# 11_MCU.net
KiCad netlist of a schematic drawn in Altium Designer
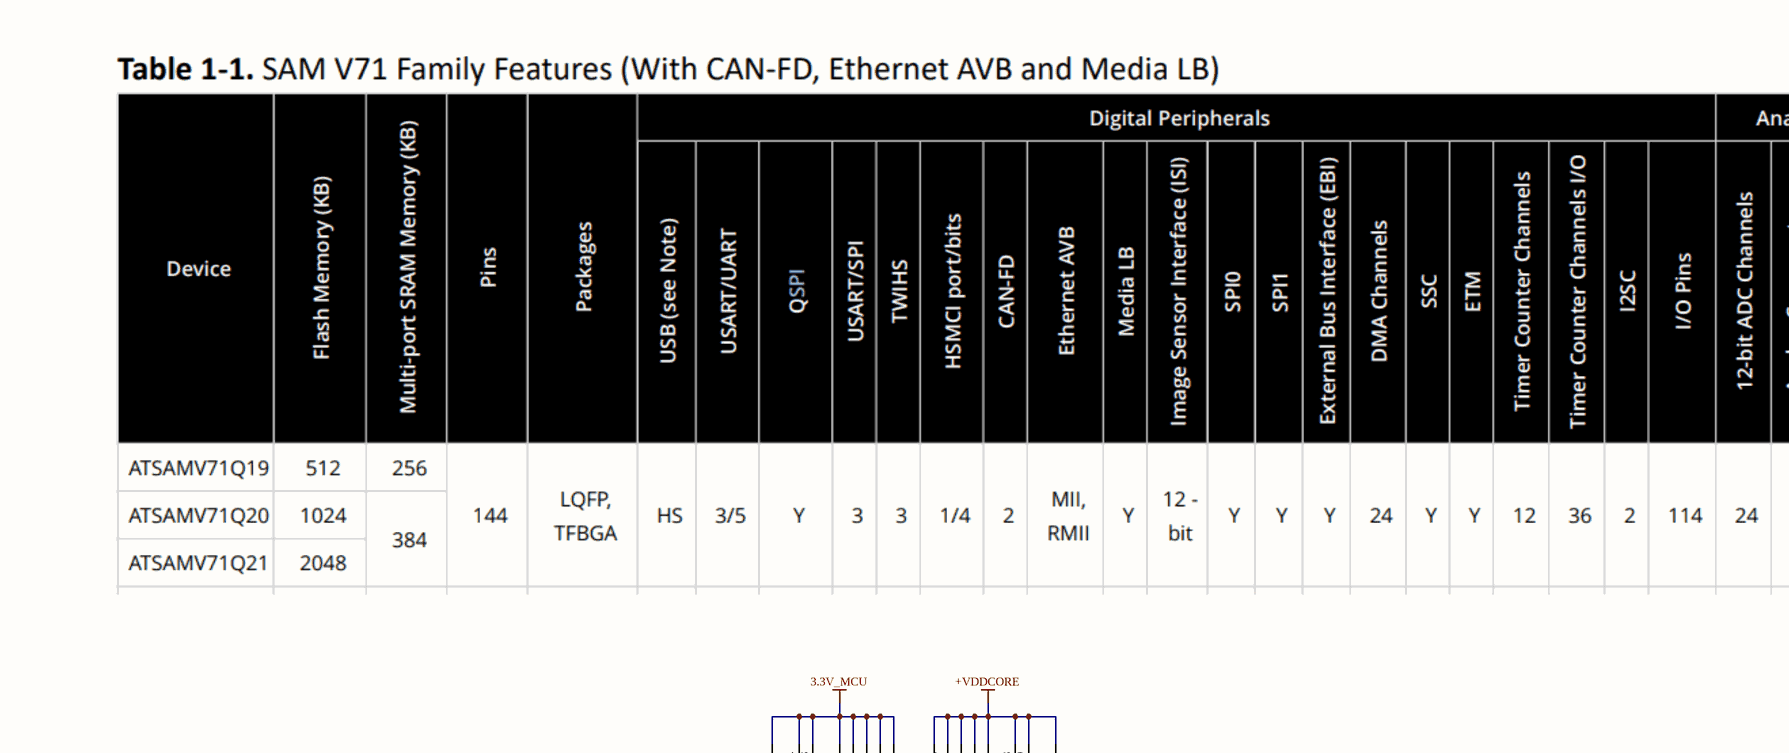
[diagram p0: 11_MCU.SchDoc, top left]
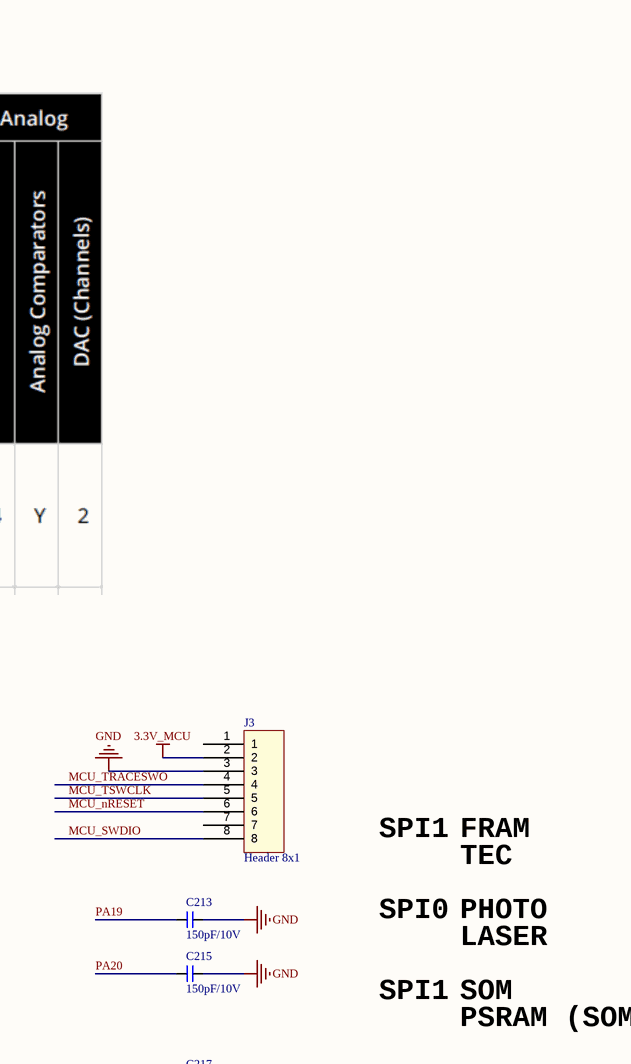
[diagram p1: 11_MCU.SchDoc, top right]
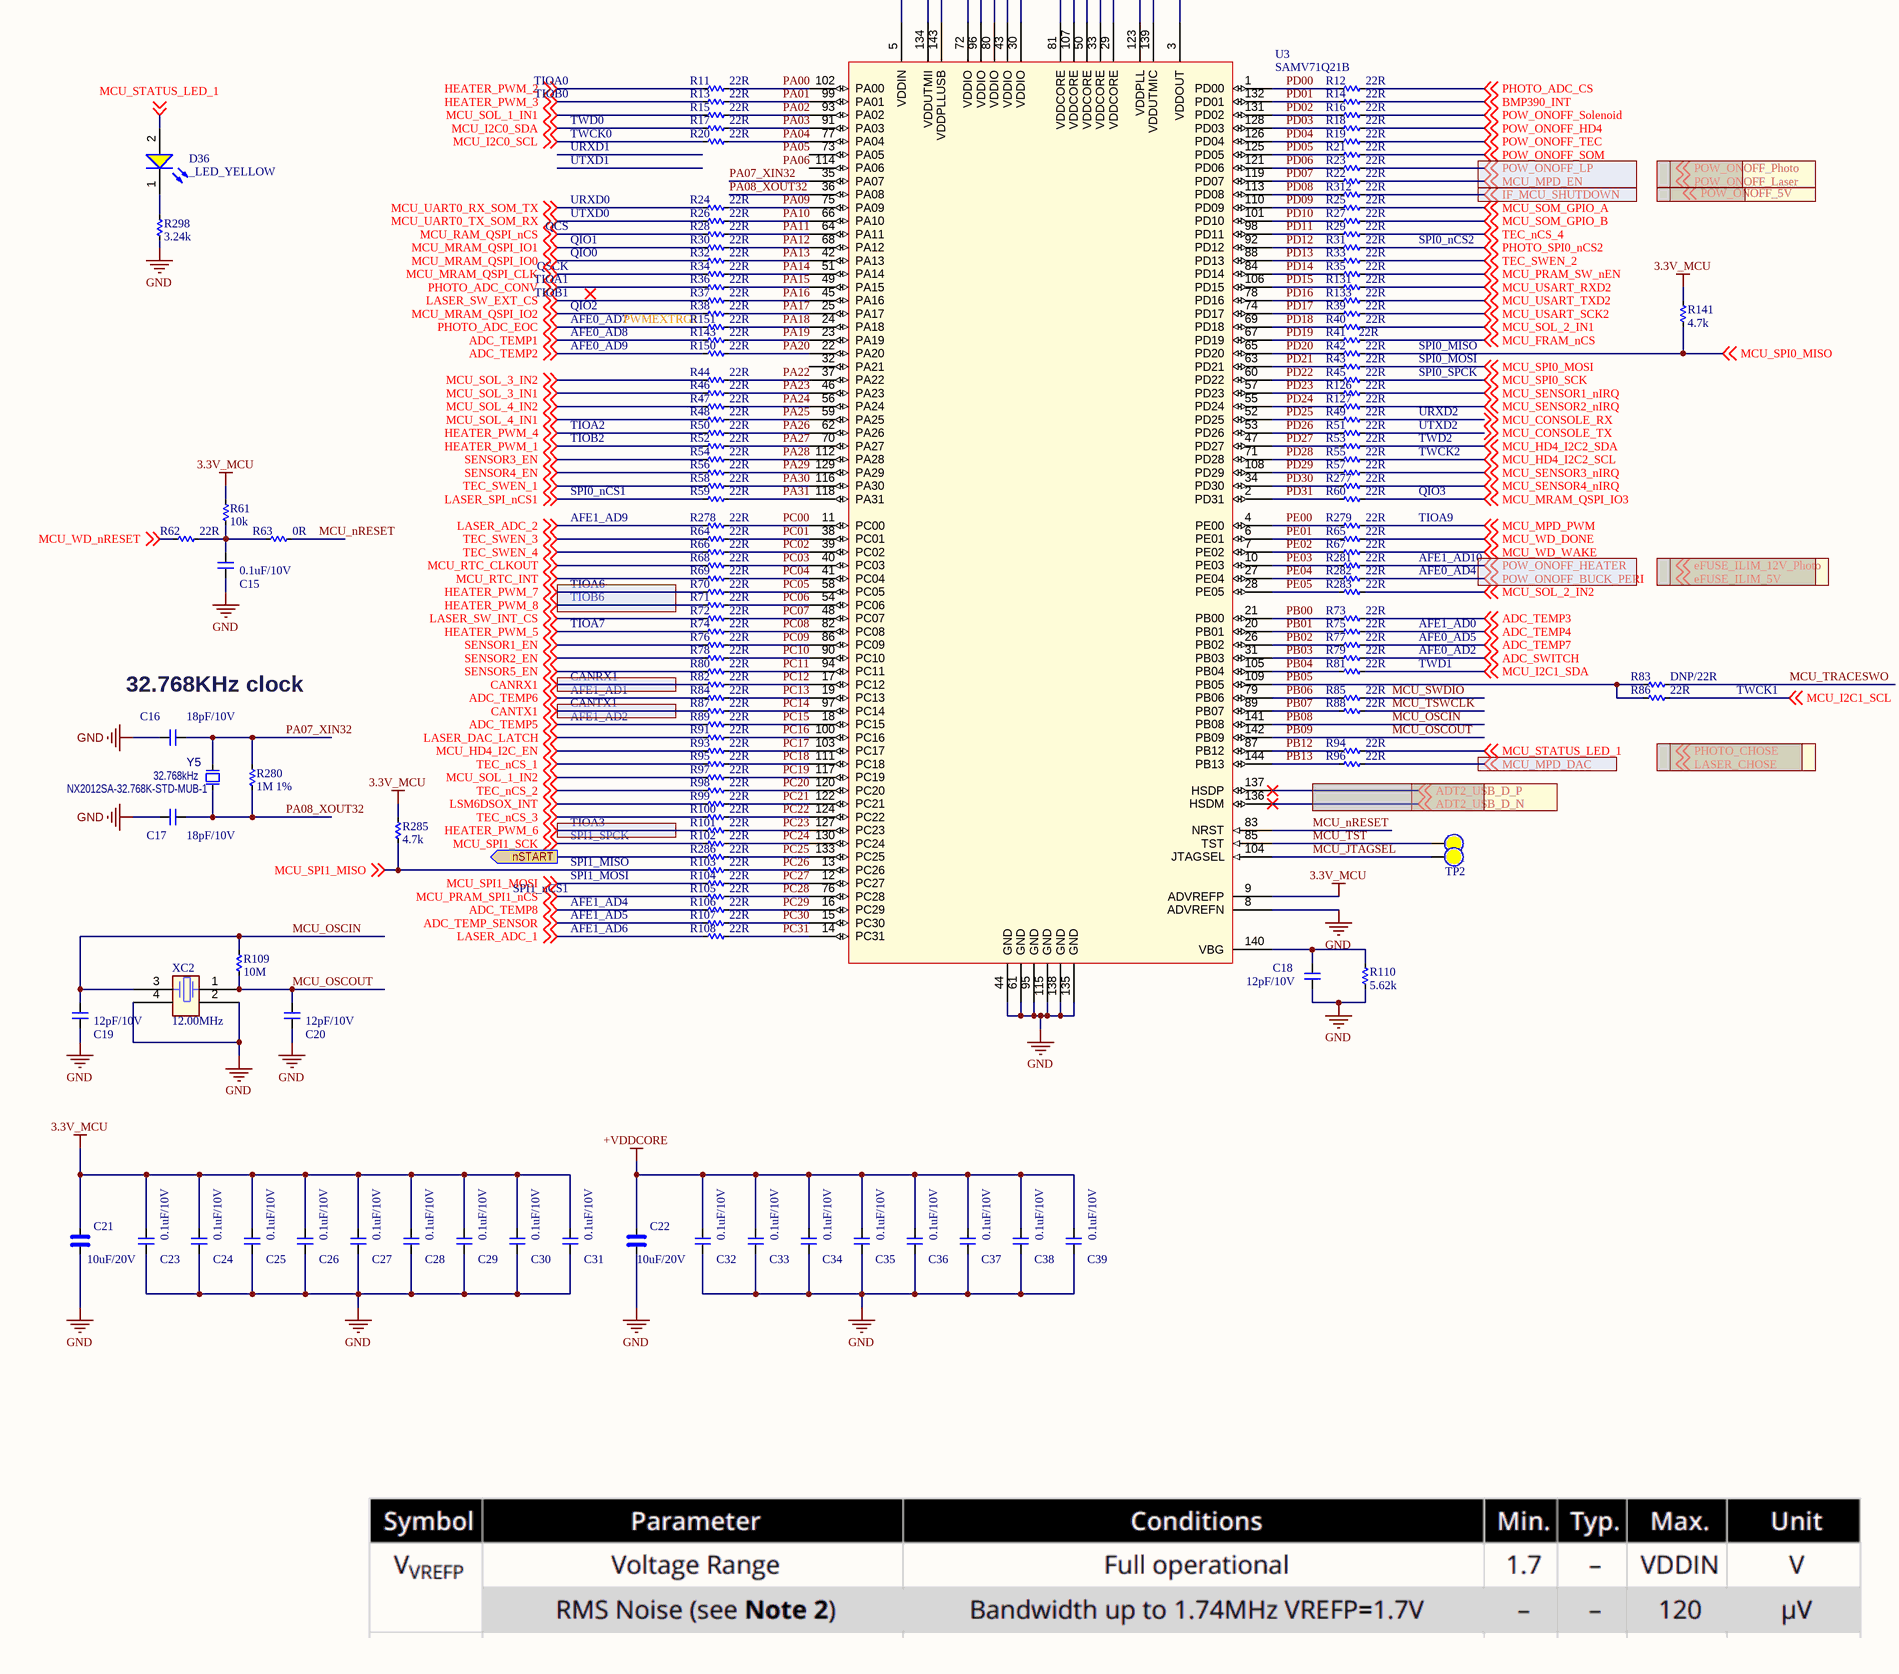
[diagram p2: 11_MCU.SchDoc, bottom left]
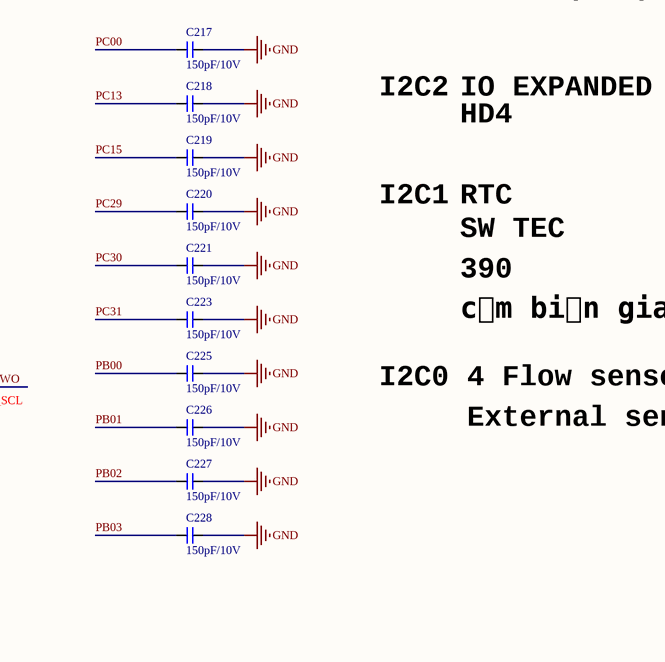
[diagram p3: 11_MCU.SchDoc, bottom right]

(export (version "E")
  (design (tool "Eeschema 10.0.6"))
  (components
    (comp (ref "C15")
      (value "0.1uF/10V")
      (footprint "CAP_C_1005X50_L")
      (description "CAP")
      (libsource (lib "LABLIB") (part "_CAP_C_2"))
    )
    (comp (ref "C16")
      (value "18pF/10V")
      (footprint "CAP_C_0603x30")
      (description "CAP")
      (libsource (lib "LABLIB") (part "_CAP_C_2"))
    )
    (comp (ref "C17")
      (value "18pF/10V")
      (footprint "CAP_C_0603x30")
      (description "CAP")
      (libsource (lib "LABLIB") (part "_CAP_C_2"))
    )
    (comp (ref "C18")
      (value "12pF/10V")
      (footprint "CAP_C_1005X50_L")
      (description "CAP")
      (libsource (lib "LABLIB") (part "_CAP_C_2"))
    )
    (comp (ref "C19")
      (value "12pF/10V")
      (footprint "CAP_C_1005X50_L")
      (description "CAP")
      (libsource (lib "LABLIB") (part "_CAP_C_2"))
    )
    (comp (ref "C20")
      (value "12pF/10V")
      (footprint "CAP_C_1005X50_L")
      (description "CAP")
      (libsource (lib "LABLIB") (part "_CAP_C_2"))
    )
    (comp (ref "C21")
      (value "10uF/20V")
      (footprint "CAP_C_2012X110")
      (description "CAP High Value")
      (libsource (lib "LABLIB") (part "_CAP_C_High_2"))
    )
    (comp (ref "C22")
      (value "10uF/20V")
      (footprint "CAP_C_2012X110")
      (description "CAP High Value")
      (libsource (lib "LABLIB") (part "_CAP_C_High_2"))
    )
    (comp (ref "C23")
      (value "0.1uF/10V")
      (footprint "CAP_C_1005X50_L")
      (description "CAP")
      (libsource (lib "LABLIB") (part "_CAP_C_2"))
    )
    (comp (ref "C24")
      (value "0.1uF/10V")
      (footprint "CAP_C_1005X50_L")
      (description "CAP")
      (libsource (lib "LABLIB") (part "_CAP_C_2"))
    )
    (comp (ref "C25")
      (value "0.1uF/10V")
      (footprint "CAP_C_1005X50_L")
      (description "CAP")
      (libsource (lib "LABLIB") (part "_CAP_C_2"))
    )
    (comp (ref "C26")
      (value "0.1uF/10V")
      (footprint "CAP_C_1005X50_L")
      (description "CAP")
      (libsource (lib "LABLIB") (part "_CAP_C_2"))
    )
    (comp (ref "C27")
      (value "0.1uF/10V")
      (footprint "CAP_C_1005X50_L")
      (description "CAP")
      (libsource (lib "LABLIB") (part "_CAP_C_2"))
    )
    (comp (ref "C28")
      (value "0.1uF/10V")
      (footprint "CAP_C_1005X50_L")
      (description "CAP")
      (libsource (lib "LABLIB") (part "_CAP_C_2"))
    )
    (comp (ref "C29")
      (value "0.1uF/10V")
      (footprint "CAP_C_1005X50_L")
      (description "CAP")
      (libsource (lib "LABLIB") (part "_CAP_C_2"))
    )
    (comp (ref "C30")
      (value "0.1uF/10V")
      (footprint "CAP_C_1005X50_L")
      (description "CAP")
      (libsource (lib "LABLIB") (part "_CAP_C_2"))
    )
    (comp (ref "C31")
      (value "0.1uF/10V")
      (footprint "CAP_C_1005X50_L")
      (description "CAP")
      (libsource (lib "LABLIB") (part "_CAP_C_2"))
    )
    (comp (ref "C32")
      (value "0.1uF/10V")
      (footprint "CAP_C_1005X50_L")
      (description "CAP")
      (libsource (lib "LABLIB") (part "_CAP_C_2"))
    )
    (comp (ref "C33")
      (value "0.1uF/10V")
      (footprint "CAP_C_1005X50_L")
      (description "CAP")
      (libsource (lib "LABLIB") (part "_CAP_C_2"))
    )
    (comp (ref "C34")
      (value "0.1uF/10V")
      (footprint "CAP_C_1005X50_L")
      (description "CAP")
      (libsource (lib "LABLIB") (part "_CAP_C_2"))
    )
    (comp (ref "C35")
      (value "0.1uF/10V")
      (footprint "CAP_C_1005X50_L")
      (description "CAP")
      (libsource (lib "LABLIB") (part "_CAP_C_2"))
    )
    (comp (ref "C36")
      (value "0.1uF/10V")
      (footprint "CAP_C_1005X50_L")
      (description "CAP")
      (libsource (lib "LABLIB") (part "_CAP_C_2"))
    )
    (comp (ref "C37")
      (value "0.1uF/10V")
      (footprint "CAP_C_1005X50_L")
      (description "CAP")
      (libsource (lib "LABLIB") (part "_CAP_C_2"))
    )
    (comp (ref "C38")
      (value "0.1uF/10V")
      (footprint "CAP_C_1005X50_L")
      (description "CAP")
      (libsource (lib "LABLIB") (part "_CAP_C_2"))
    )
    (comp (ref "C39")
      (value "0.1uF/10V")
      (footprint "CAP_C_1005X50_L")
      (description "CAP")
      (libsource (lib "LABLIB") (part "_CAP_C_2"))
    )
    (comp (ref "C213")
      (value "150pF/10V")
      (footprint "CAP_C_0603x30")
      (description "CAP")
      (libsource (lib "LABLIB") (part "_CAP_C_2"))
    )
    (comp (ref "C215")
      (value "150pF/10V")
      (footprint "CAP_C_0603x30")
      (description "CAP")
      (libsource (lib "LABLIB") (part "_CAP_C_2"))
    )
    (comp (ref "C217")
      (value "150pF/10V")
      (footprint "CAP_C_0603x30")
      (description "CAP")
      (libsource (lib "LABLIB") (part "_CAP_C_2"))
    )
    (comp (ref "C218")
      (value "150pF/10V")
      (footprint "CAP_C_0603x30")
      (description "CAP")
      (libsource (lib "LABLIB") (part "_CAP_C_2"))
    )
    (comp (ref "C219")
      (value "150pF/10V")
      (footprint "CAP_C_0603x30")
      (description "CAP")
      (libsource (lib "LABLIB") (part "_CAP_C_2"))
    )
    (comp (ref "C220")
      (value "150pF/10V")
      (footprint "CAP_C_0603x30")
      (description "CAP")
      (libsource (lib "LABLIB") (part "_CAP_C_2"))
    )
    (comp (ref "C221")
      (value "150pF/10V")
      (footprint "CAP_C_0603x30")
      (description "CAP")
      (libsource (lib "LABLIB") (part "_CAP_C_2"))
    )
    (comp (ref "C223")
      (value "150pF/10V")
      (footprint "CAP_C_0603x30")
      (description "CAP")
      (libsource (lib "LABLIB") (part "_CAP_C_2"))
    )
    (comp (ref "C225")
      (value "150pF/10V")
      (footprint "CAP_C_0603x30")
      (description "CAP")
      (libsource (lib "LABLIB") (part "_CAP_C_2"))
    )
    (comp (ref "C226")
      (value "150pF/10V")
      (footprint "CAP_C_0603x30")
      (description "CAP")
      (libsource (lib "LABLIB") (part "_CAP_C_2"))
    )
    (comp (ref "C227")
      (value "150pF/10V")
      (footprint "CAP_C_0603x30")
      (description "CAP")
      (libsource (lib "LABLIB") (part "_CAP_C_2"))
    )
    (comp (ref "C228")
      (value "150pF/10V")
      (footprint "CAP_C_0603x30")
      (description "CAP")
      (libsource (lib "LABLIB") (part "_CAP_C_2"))
    )
    (comp (ref "D36")
      (value "_LED_YELLOW")
      (footprint "LED_0402")
      (libsource (lib "LABLIB") (part "_LED_YELLOW"))
    )
    (comp (ref "J3")
      (value "Header 8x1")
      (footprint "SAMTEC_TSM-108-01-L-SV-P-TR")
      (libsource (lib "LABLIB") (part "Header 8x1"))
    )
    (comp (ref "R11")
      (value "22R")
      (footprint "RES_C_0603X30")
      (description "RES")
      (libsource (lib "LABLIB") (part "_RES_B_2"))
    )
    (comp (ref "R12")
      (value "22R")
      (footprint "RES_C_0603X30")
      (description "RES")
      (libsource (lib "LABLIB") (part "_RES_B_2"))
    )
    (comp (ref "R13")
      (value "22R")
      (footprint "RES_C_0603X30")
      (description "RES")
      (libsource (lib "LABLIB") (part "_RES_B_2"))
    )
    (comp (ref "R14")
      (value "22R")
      (footprint "RES_C_0603X30")
      (description "RES")
      (libsource (lib "LABLIB") (part "_RES_B_2"))
    )
    (comp (ref "R15")
      (value "22R")
      (footprint "RES_C_0603X30")
      (description "RES")
      (libsource (lib "LABLIB") (part "_RES_B_2"))
    )
    (comp (ref "R16")
      (value "22R")
      (footprint "RES_C_0603X30")
      (description "RES")
      (libsource (lib "LABLIB") (part "_RES_B_2"))
    )
    (comp (ref "R17")
      (value "22R")
      (footprint "RES_C_0603X30")
      (description "RES")
      (libsource (lib "LABLIB") (part "_RES_B_2"))
    )
    (comp (ref "R18")
      (value "22R")
      (footprint "RES_C_0603X30")
      (description "RES")
      (libsource (lib "LABLIB") (part "_RES_B_2"))
    )
    (comp (ref "R19")
      (value "22R")
      (footprint "RES_C_0603X30")
      (description "RES")
      (libsource (lib "LABLIB") (part "_RES_B_2"))
    )
    (comp (ref "R20")
      (value "22R")
      (footprint "RES_C_0603X30")
      (description "RES")
      (libsource (lib "LABLIB") (part "_RES_B_2"))
    )
    (comp (ref "R21")
      (value "22R")
      (footprint "RES_C_0603X30")
      (description "RES")
      (libsource (lib "LABLIB") (part "_RES_B_2"))
    )
    (comp (ref "R22")
      (value "22R")
      (footprint "RES_C_0603X30")
      (description "RES")
      (libsource (lib "LABLIB") (part "_RES_B_2"))
    )
    (comp (ref "R23")
      (value "22R")
      (footprint "RES_C_0603X30")
      (description "RES")
      (libsource (lib "LABLIB") (part "_RES_B_2"))
    )
    (comp (ref "R24")
      (value "22R")
      (footprint "RES_C_0603X30")
      (description "RES")
      (libsource (lib "LABLIB") (part "_RES_B_2"))
    )
    (comp (ref "R25")
      (value "22R")
      (footprint "RES_C_0603X30")
      (description "RES")
      (libsource (lib "LABLIB") (part "_RES_B_2"))
    )
    (comp (ref "R26")
      (value "22R")
      (footprint "RES_C_0603X30")
      (description "RES")
      (libsource (lib "LABLIB") (part "_RES_B_2"))
    )
    (comp (ref "R27")
      (value "22R")
      (footprint "RES_C_0603X30")
      (description "RES")
      (libsource (lib "LABLIB") (part "_RES_B_2"))
    )
    (comp (ref "R28")
      (value "22R")
      (footprint "RES_C_0603X30")
      (description "RES")
      (libsource (lib "LABLIB") (part "_RES_B_2"))
    )
    (comp (ref "R29")
      (value "22R")
      (footprint "RES_C_0603X30")
      (description "RES")
      (libsource (lib "LABLIB") (part "_RES_B_2"))
    )
    (comp (ref "R30")
      (value "22R")
      (footprint "RES_C_0603X30")
      (description "RES")
      (libsource (lib "LABLIB") (part "_RES_B_2"))
    )
    (comp (ref "R31")
      (value "22R")
      (footprint "RES_C_0603X30")
      (description "RES")
      (libsource (lib "LABLIB") (part "_RES_B_2"))
    )
    (comp (ref "R32")
      (value "22R")
      (footprint "RES_C_0603X30")
      (description "RES")
      (libsource (lib "LABLIB") (part "_RES_B_2"))
    )
    (comp (ref "R33")
      (value "22R")
      (footprint "RES_C_0603X30")
      (description "RES")
      (libsource (lib "LABLIB") (part "_RES_B_2"))
    )
    (comp (ref "R34")
      (value "22R")
      (footprint "RES_C_0603X30")
      (description "RES")
      (libsource (lib "LABLIB") (part "_RES_B_2"))
    )
    (comp (ref "R35")
      (value "22R")
      (footprint "RES_C_0603X30")
      (description "RES")
      (libsource (lib "LABLIB") (part "_RES_B_2"))
    )
    (comp (ref "R36")
      (value "22R")
      (footprint "RES_C_0603X30")
      (description "RES")
      (libsource (lib "LABLIB") (part "_RES_B_2"))
    )
    (comp (ref "R37")
      (value "22R")
      (footprint "RES_C_0603X30")
      (description "RES")
      (libsource (lib "LABLIB") (part "_RES_B_2"))
    )
    (comp (ref "R38")
      (value "22R")
      (footprint "RES_C_0603X30")
      (description "RES")
      (libsource (lib "LABLIB") (part "_RES_B_2"))
    )
    (comp (ref "R39")
      (value "22R")
      (footprint "RES_C_0603X30")
      (description "RES")
      (libsource (lib "LABLIB") (part "_RES_B_2"))
    )
    (comp (ref "R40")
      (value "22R")
      (footprint "RES_C_0603X30")
      (description "RES")
      (libsource (lib "LABLIB") (part "_RES_B_2"))
    )
    (comp (ref "R41")
      (value "22R")
      (footprint "RES_C_0603X30")
      (description "RES")
      (libsource (lib "LABLIB") (part "_RES_B_2"))
    )
    (comp (ref "R42")
      (value "22R")
      (footprint "RES_C_0603X30")
      (description "RES")
      (libsource (lib "LABLIB") (part "_RES_B_2"))
    )
    (comp (ref "R43")
      (value "22R")
      (footprint "RES_C_0603X30")
      (description "RES")
      (libsource (lib "LABLIB") (part "_RES_B_2"))
    )
    (comp (ref "R44")
      (value "22R")
      (footprint "RES_C_0603X30")
      (description "RES")
      (libsource (lib "LABLIB") (part "_RES_B_2"))
    )
    (comp (ref "R45")
      (value "22R")
      (footprint "RES_C_0603X30")
      (description "RES")
      (libsource (lib "LABLIB") (part "_RES_B_2"))
    )
    (comp (ref "R46")
      (value "22R")
      (footprint "RES_C_0603X30")
      (description "RES")
      (libsource (lib "LABLIB") (part "_RES_B_2"))
    )
    (comp (ref "R47")
      (value "22R")
      (footprint "RES_C_0603X30")
      (description "RES")
      (libsource (lib "LABLIB") (part "_RES_B_2"))
    )
    (comp (ref "R48")
      (value "22R")
      (footprint "RES_C_0603X30")
      (description "RES")
      (libsource (lib "LABLIB") (part "_RES_B_2"))
    )
    (comp (ref "R49")
      (value "22R")
      (footprint "RES_C_0603X30")
      (description "RES")
      (libsource (lib "LABLIB") (part "_RES_B_2"))
    )
    (comp (ref "R50")
      (value "22R")
      (footprint "RES_C_0603X30")
      (description "RES")
      (libsource (lib "LABLIB") (part "_RES_B_2"))
    )
    (comp (ref "R51")
      (value "22R")
      (footprint "RES_C_0603X30")
      (description "RES")
      (libsource (lib "LABLIB") (part "_RES_B_2"))
    )
    (comp (ref "R52")
      (value "22R")
      (footprint "RES_C_0603X30")
      (description "RES")
      (libsource (lib "LABLIB") (part "_RES_B_2"))
    )
    (comp (ref "R53")
      (value "22R")
      (footprint "RES_C_0603X30")
      (description "RES")
      (libsource (lib "LABLIB") (part "_RES_B_2"))
    )
    (comp (ref "R54")
      (value "22R")
      (footprint "RES_C_0603X30")
      (description "RES")
      (libsource (lib "LABLIB") (part "_RES_B_2"))
    )
    (comp (ref "R55")
      (value "22R")
      (footprint "RES_C_0603X30")
      (description "RES")
      (libsource (lib "LABLIB") (part "_RES_B_2"))
    )
    (comp (ref "R56")
      (value "22R")
      (footprint "RES_C_0603X30")
      (description "RES")
      (libsource (lib "LABLIB") (part "_RES_B_2"))
    )
    (comp (ref "R57")
      (value "22R")
      (footprint "RES_C_0603X30")
      (description "RES")
      (libsource (lib "LABLIB") (part "_RES_B_2"))
    )
    (comp (ref "R58")
      (value "22R")
      (footprint "RES_C_0603X30")
      (description "RES")
      (libsource (lib "LABLIB") (part "_RES_B_2"))
    )
    (comp (ref "R59")
      (value "22R")
      (footprint "RES_C_0603X30")
      (description "RES")
      (libsource (lib "LABLIB") (part "_RES_B_2"))
    )
    (comp (ref "R60")
      (value "22R")
      (footprint "RES_C_0603X30")
      (description "RES")
      (libsource (lib "LABLIB") (part "_RES_B_2"))
    )
    (comp (ref "R61")
      (value "10k")
      (footprint "RES_C_1005x30_L")
      (description "RES")
      (libsource (lib "LABLIB") (part "_RES_B_2"))
    )
    (comp (ref "R62")
      (value "22R")
      (footprint "RES_C_1005x30_L")
      (description "RES")
      (libsource (lib "LABLIB") (part "_RES_B_2"))
    )
    (comp (ref "R63")
      (value "0R")
      (footprint "RES_C_0603X30")
      (description "RES")
      (libsource (lib "LABLIB") (part "_RES_B_2"))
    )
    (comp (ref "R64")
      (value "22R")
      (footprint "RES_C_0603X30")
      (description "RES")
      (libsource (lib "LABLIB") (part "_RES_B_2"))
    )
    (comp (ref "R65")
      (value "22R")
      (footprint "RES_C_0603X30")
      (description "RES")
      (libsource (lib "LABLIB") (part "_RES_B_2"))
    )
    (comp (ref "R66")
      (value "22R")
      (footprint "RES_C_0603X30")
      (description "RES")
      (libsource (lib "LABLIB") (part "_RES_B_2"))
    )
    (comp (ref "R67")
      (value "22R")
      (footprint "RES_C_0603X30")
      (description "RES")
      (libsource (lib "LABLIB") (part "_RES_B_2"))
    )
    (comp (ref "R68")
      (value "22R")
      (footprint "RES_C_0603X30")
      (description "RES")
      (libsource (lib "LABLIB") (part "_RES_B_2"))
    )
    (comp (ref "R69")
      (value "22R")
      (footprint "RES_C_0603X30")
      (description "RES")
      (libsource (lib "LABLIB") (part "_RES_B_2"))
    )
    (comp (ref "R70")
      (value "22R")
      (footprint "RES_C_0603X30")
      (description "RES")
      (libsource (lib "LABLIB") (part "_RES_B_2"))
    )
    (comp (ref "R71")
      (value "22R")
      (footprint "RES_C_0603X30")
      (description "RES")
      (libsource (lib "LABLIB") (part "_RES_B_2"))
    )
    (comp (ref "R72")
      (value "22R")
      (footprint "RES_C_0603X30")
      (description "RES")
      (libsource (lib "LABLIB") (part "_RES_B_2"))
    )
    (comp (ref "R73")
      (value "22R")
      (footprint "RES_C_0603X30")
      (description "RES")
      (libsource (lib "LABLIB") (part "_RES_B_2"))
    )
    (comp (ref "R74")
      (value "22R")
      (footprint "RES_C_0603X30")
      (description "RES")
      (libsource (lib "LABLIB") (part "_RES_B_2"))
    )
    (comp (ref "R75")
      (value "22R")
      (footprint "RES_C_0603X30")
      (description "RES")
      (libsource (lib "LABLIB") (part "_RES_B_2"))
    )
    (comp (ref "R76")
      (value "22R")
      (footprint "RES_C_0603X30")
      (description "RES")
      (libsource (lib "LABLIB") (part "_RES_B_2"))
    )
    (comp (ref "R77")
      (value "22R")
      (footprint "RES_C_0603X30")
      (description "RES")
      (libsource (lib "LABLIB") (part "_RES_B_2"))
    )
    (comp (ref "R78")
      (value "22R")
      (footprint "RES_C_0603X30")
      (description "RES")
      (libsource (lib "LABLIB") (part "_RES_B_2"))
    )
    (comp (ref "R79")
      (value "22R")
      (footprint "RES_C_0603X30")
      (description "RES")
      (libsource (lib "LABLIB") (part "_RES_B_2"))
    )
    (comp (ref "R80")
      (value "22R")
      (footprint "RES_C_0603X30")
      (description "RES")
      (libsource (lib "LABLIB") (part "_RES_B_2"))
    )
    (comp (ref "R81")
      (value "22R")
      (footprint "RES_C_0603X30")
      (description "RES")
      (libsource (lib "LABLIB") (part "_RES_B_2"))
    )
    (comp (ref "R82")
      (value "22R")
      (footprint "RES_C_0603X30")
      (description "RES")
      (libsource (lib "LABLIB") (part "_RES_B_2"))
    )
    (comp (ref "R83")
      (value "DNP/22R")
      (footprint "RES_C_0603X30")
      (description "RES")
      (libsource (lib "LABLIB") (part "_RES_B_2"))
    )
    (comp (ref "R84")
      (value "22R")
      (footprint "RES_C_0603X30")
      (description "RES")
      (libsource (lib "LABLIB") (part "_RES_B_2"))
    )
    (comp (ref "R85")
      (value "22R")
      (footprint "RES_C_0603X30")
      (description "RES")
      (libsource (lib "LABLIB") (part "_RES_B_2"))
    )
    (comp (ref "R86")
      (value "22R")
      (footprint "RES_C_0603X30")
      (description "RES")
      (libsource (lib "LABLIB") (part "_RES_B_2"))
    )
    (comp (ref "R87")
      (value "22R")
      (footprint "RES_C_0603X30")
      (description "RES")
      (libsource (lib "LABLIB") (part "_RES_B_2"))
    )
    (comp (ref "R88")
      (value "22R")
      (footprint "RES_C_0603X30")
      (description "RES")
      (libsource (lib "LABLIB") (part "_RES_B_2"))
    )
    (comp (ref "R89")
      (value "22R")
      (footprint "RES_C_0603X30")
      (description "RES")
      (libsource (lib "LABLIB") (part "_RES_B_2"))
    )
    (comp (ref "R91")
      (value "22R")
      (footprint "RES_C_0603X30")
      (description "RES")
      (libsource (lib "LABLIB") (part "_RES_B_2"))
    )
    (comp (ref "R93")
      (value "22R")
      (footprint "RES_C_0603X30")
      (description "RES")
      (libsource (lib "LABLIB") (part "_RES_B_2"))
    )
    (comp (ref "R94")
      (value "22R")
      (footprint "RES_C_0603X30")
      (description "RES")
      (libsource (lib "LABLIB") (part "_RES_B_2"))
    )
    (comp (ref "R95")
      (value "22R")
      (footprint "RES_C_0603X30")
      (description "RES")
      (libsource (lib "LABLIB") (part "_RES_B_2"))
    )
    (comp (ref "R96")
      (value "22R")
      (footprint "RES_C_0603X30")
      (description "RES")
      (libsource (lib "LABLIB") (part "_RES_B_2"))
    )
    (comp (ref "R97")
      (value "22R")
      (footprint "RES_C_0603X30")
      (description "RES")
      (libsource (lib "LABLIB") (part "_RES_B_2"))
    )
    (comp (ref "R98")
      (value "22R")
      (footprint "RES_C_0603X30")
      (description "RES")
      (libsource (lib "LABLIB") (part "_RES_B_2"))
    )
    (comp (ref "R99")
      (value "22R")
      (footprint "RES_C_0603X30")
      (description "RES")
      (libsource (lib "LABLIB") (part "_RES_B_2"))
    )
    (comp (ref "R100")
      (value "22R")
      (footprint "RES_C_0603X30")
      (description "RES")
      (libsource (lib "LABLIB") (part "_RES_B_2"))
    )
    (comp (ref "R101")
      (value "22R")
      (footprint "RES_C_0603X30")
      (description "RES")
      (libsource (lib "LABLIB") (part "_RES_B_2"))
    )
    (comp (ref "R102")
      (value "22R")
      (footprint "RES_C_0603X30")
      (description "RES")
      (libsource (lib "LABLIB") (part "_RES_B_2"))
    )
    (comp (ref "R103")
      (value "22R")
      (footprint "RES_C_0603X30")
      (description "RES")
      (libsource (lib "LABLIB") (part "_RES_B_2"))
    )
    (comp (ref "R104")
      (value "22R")
      (footprint "RES_C_0603X30")
      (description "RES")
      (libsource (lib "LABLIB") (part "_RES_B_2"))
    )
    (comp (ref "R105")
      (value "22R")
      (footprint "RES_C_0603X30")
      (description "RES")
      (libsource (lib "LABLIB") (part "_RES_B_2"))
    )
    (comp (ref "R106")
      (value "22R")
      (footprint "RES_C_0603X30")
      (description "RES")
      (libsource (lib "LABLIB") (part "_RES_B_2"))
    )
    (comp (ref "R107")
      (value "22R")
      (footprint "RES_C_0603X30")
      (description "RES")
      (libsource (lib "LABLIB") (part "_RES_B_2"))
    )
    (comp (ref "R108")
      (value "22R")
      (footprint "RES_C_0603X30")
      (description "RES")
      (libsource (lib "LABLIB") (part "_RES_B_2"))
    )
    (comp (ref "R109")
      (value "10M")
      (footprint "RES_C_1005x30_L")
      (description "RES")
      (libsource (lib "LABLIB") (part "_RES_B_2"))
    )
    (comp (ref "R110")
      (value "5.62k")
      (footprint "RES_C_1005x30_L")
      (description "RES")
      (libsource (lib "LABLIB") (part "_RES_B_2"))
    )
    (comp (ref "R126")
      (value "22R")
      (footprint "RES_C_0603X30")
      (description "RES")
      (libsource (lib "LABLIB") (part "_RES_B_2"))
    )
    (comp (ref "R127")
      (value "22R")
      (footprint "RES_C_0603X30")
      (description "RES")
      (libsource (lib "LABLIB") (part "_RES_B_2"))
    )
    (comp (ref "R131")
      (value "22R")
      (footprint "RES_C_0603X30")
      (description "RES")
      (libsource (lib "LABLIB") (part "_RES_B_2"))
    )
    (comp (ref "R133")
      (value "22R")
      (footprint "RES_C_0603X30")
      (description "RES")
      (libsource (lib "LABLIB") (part "_RES_B_2"))
    )
    (comp (ref "R141")
      (value "4.7k")
      (footprint "RES_C_0603X30")
      (description "RES")
      (libsource (lib "LABLIB") (part "_RES_B_2"))
    )
    (comp (ref "R143")
      (value "22R")
      (footprint "RES_C_0603X30")
      (description "RES")
      (libsource (lib "LABLIB") (part "_RES_B_2"))
    )
    (comp (ref "R150")
      (value "22R")
      (footprint "RES_C_0603X30")
      (description "RES")
      (libsource (lib "LABLIB") (part "_RES_B_2"))
    )
    (comp (ref "R151")
      (value "22R")
      (footprint "RES_C_0603X30")
      (description "RES")
      (libsource (lib "LABLIB") (part "_RES_B_2"))
    )
    (comp (ref "R277")
      (value "22R")
      (footprint "RES_C_0603X30")
      (description "RES")
      (libsource (lib "LABLIB") (part "_RES_B_2"))
    )
    (comp (ref "R278")
      (value "22R")
      (footprint "RES_C_0603X30")
      (description "RES")
      (libsource (lib "LABLIB") (part "_RES_B_2"))
    )
    (comp (ref "R279")
      (value "22R")
      (footprint "RES_C_0603X30")
      (description "RES")
      (libsource (lib "LABLIB") (part "_RES_B_2"))
    )
    (comp (ref "R280")
      (value "1M 1%")
      (footprint "RES_C_1005x30_L")
      (description "RES")
      (libsource (lib "LABLIB") (part "_RES_B_2"))
    )
    (comp (ref "R281")
      (value "22R")
      (footprint "RES_C_0603X30")
      (description "RES")
      (libsource (lib "LABLIB") (part "_RES_B_2"))
    )
    (comp (ref "R282")
      (value "22R")
      (footprint "RES_C_0603X30")
      (description "RES")
      (libsource (lib "LABLIB") (part "_RES_B_2"))
    )
    (comp (ref "R283")
      (value "22R")
      (footprint "RES_C_0603X30")
      (description "RES")
      (libsource (lib "LABLIB") (part "_RES_B_2"))
    )
    (comp (ref "R285")
      (value "4.7k")
      (footprint "RES_C_0603X30")
      (description "RES")
      (libsource (lib "LABLIB") (part "_RES_B_2"))
    )
    (comp (ref "R286")
      (value "22R")
      (footprint "RES_C_0603X30")
      (description "RES")
      (libsource (lib "LABLIB") (part "_RES_B_2"))
    )
    (comp (ref "R298")
      (value "3.24k")
      (footprint "RES_C_1005x30_L")
      (description "RES")
      (libsource (lib "LABLIB") (part "_RES_B_2"))
    )
    (comp (ref "R312")
      (value "22R")
      (footprint "RES_C_0603X30")
      (description "RES")
      (libsource (lib "LABLIB") (part "_RES_B_2"))
    )
    (comp (ref "TP1")
      (value "~")
      (footprint "TP_1mm_SMD")
      (description "Test Point")
      (libsource (lib "LABLIB") (part "Test Point"))
    )
    (comp (ref "TP2")
      (value "~")
      (footprint "TP_1mm_SMD")
      (description "Test Point")
      (libsource (lib "LABLIB") (part "Test Point"))
    )
    (comp (ref "U3")
      (value "SAMV71Q21B")
      (footprint "AP6-00118")
      (description "SAM 32-bit ARM Cortex-M* RISC MCU, SAMV71B Series, QFP144")
      (fields (field (name "MANUFACTURER") "MICROCHIP") (field (name "MPN") "ATSAMV71Q21B-AAB"))
      (libsource (lib "AltiumDbLib") (part "SAMV7_LQFP144"))
    )
    (comp (ref "XC2")
      (value "12.00MHz")
      (footprint "AP7-00039")
      (description "Fox FQ5032B 12.0MHz SMD crystal 738B-12")
      (fields (field (name "TOLERANCE") "Â±30ppm") (field (name "MANUFACTURER") "Fox  Electronics"))
      (libsource (lib "AltiumDbLib") (part "CRYSTAL1324"))
    )
    (comp (ref "Y5")
      (value "32.768kHz")
      (footprint "CRYSTAL_NX2012SA")
      (description "Crystal")
      (fields
        (field (name "TOLERANCE") "±20ppm")
        (field (name "MANUFACTURER PART NUMBER 1") "NX2012SA-32.768K-STD-MUB-1")
        (field (name "Comment") "Crystal 2 Pins")
        (field (name "OWNER") "Jamus Griego")
      )
      (libsource (lib "LABLIB") (part "OSC_32.768kHz"))
    )
  )
  (nets
    (net (code "1") (name "+VDDCORE") (class "Default")
      (node (ref "C22") (pin "1") (pinfunction "1_1") (pintype "passive"))
      (node (ref "C32") (pin "2") (pinfunction "2_2") (pintype "passive"))
      (node (ref "C33") (pin "2") (pinfunction "2_2") (pintype "passive"))
      (node (ref "C34") (pin "2") (pinfunction "2_2") (pintype "passive"))
      (node (ref "C35") (pin "2") (pinfunction "2_2") (pintype "passive"))
      (node (ref "C36") (pin "2") (pinfunction "2_2") (pintype "passive"))
      (node (ref "C37") (pin "2") (pinfunction "2_2") (pintype "passive"))
      (node (ref "C38") (pin "2") (pinfunction "2_2") (pintype "passive"))
      (node (ref "C39") (pin "2") (pinfunction "2_2") (pintype "passive"))
      (node (ref "U3") (pin "107") (pinfunction "VDDCORE_107") (pintype "power_in"))
      (node (ref "U3") (pin "123") (pinfunction "VDDPLL_123") (pintype "power_in"))
      (node (ref "U3") (pin "139") (pinfunction "VDDUTMIC_139") (pintype "power_in"))
      (node (ref "U3") (pin "29") (pinfunction "VDDCORE_29") (pintype "power_in"))
      (node (ref "U3") (pin "3") (pinfunction "VDDOUT_3") (pintype "power_in"))
      (node (ref "U3") (pin "33") (pinfunction "VDDCORE_33") (pintype "power_in"))
      (node (ref "U3") (pin "50") (pinfunction "VDDCORE_50") (pintype "power_in"))
      (node (ref "U3") (pin "81") (pinfunction "VDDCORE_81") (pintype "power_in"))
    )
    (net (code "2") (name "/MCU_JTAGSEL") (class "Default")
      (node (ref "TP2") (pin "0") (pinfunction "0_0") (pintype "passive"))
      (node (ref "U3") (pin "104") (pinfunction "JTAGSEL_104") (pintype "input"))
    )
    (net (code "3") (name "/MCU_OSCIN") (class "Default")
      (node (ref "C19") (pin "2") (pinfunction "2_2") (pintype "passive"))
      (node (ref "R109") (pin "2") (pinfunction "2_2") (pintype "passive"))
      (node (ref "U3") (pin "141") (pinfunction "PB08_141") (pintype "bidirectional"))
      (node (ref "XC2") (pin "3") (pinfunction "3_3") (pintype "passive"))
    )
    (net (code "4") (name "/MCU_OSCOUT") (class "Default")
      (node (ref "C20") (pin "2") (pinfunction "2_2") (pintype "passive"))
      (node (ref "R109") (pin "1") (pinfunction "1_1") (pintype "passive"))
      (node (ref "U3") (pin "142") (pinfunction "PB09_142") (pintype "bidirectional"))
      (node (ref "XC2") (pin "1") (pinfunction "1_1") (pintype "passive"))
    )
    (net (code "5") (name "/MCU_SWDIO") (class "Default")
      (node (ref "J3") (pin "8") (pinfunction "8_8") (pintype "passive"))
      (node (ref "R85") (pin "1") (pinfunction "1_1") (pintype "passive"))
    )
    (net (code "6") (name "/MCU_TRACESWO") (class "Default")
      (node (ref "J3") (pin "4") (pinfunction "4_4") (pintype "passive"))
      (node (ref "R83") (pin "1") (pinfunction "1_1") (pintype "passive"))
    )
    (net (code "7") (name "/MCU_TST") (class "Default")
      (node (ref "TP1") (pin "0") (pinfunction "0_0") (pintype "passive"))
      (node (ref "U3") (pin "85") (pinfunction "TST_85") (pintype "input"))
    )
    (net (code "8") (name "/MCU_TSWCLK") (class "Default")
      (node (ref "J3") (pin "5") (pinfunction "5_5") (pintype "passive"))
      (node (ref "R88") (pin "1") (pinfunction "1_1") (pintype "passive"))
    )
    (net (code "9") (name "/MCU_nRESET") (class "Default")
      (node (ref "J3") (pin "6") (pinfunction "6_6") (pintype "passive"))
      (node (ref "R63") (pin "1") (pinfunction "1_1") (pintype "passive"))
      (node (ref "U3") (pin "83") (pinfunction "NRST_83") (pintype "input"))
    )
    (net (code "10") (name "/PA00") (class "Default")
      (node (ref "R11") (pin "1") (pinfunction "1_1") (pintype "passive"))
      (node (ref "U3") (pin "102") (pinfunction "PA00_102") (pintype "bidirectional"))
    )
    (net (code "11") (name "/PA01") (class "Default")
      (node (ref "R13") (pin "1") (pinfunction "1_1") (pintype "passive"))
      (node (ref "U3") (pin "99") (pinfunction "PA01_99") (pintype "bidirectional"))
    )
    (net (code "12") (name "/PA02") (class "Default")
      (node (ref "R15") (pin "1") (pinfunction "1_1") (pintype "passive"))
      (node (ref "U3") (pin "93") (pinfunction "PA02_93") (pintype "bidirectional"))
    )
    (net (code "13") (name "/PA03") (class "Default")
      (node (ref "R17") (pin "1") (pinfunction "1_1") (pintype "passive"))
      (node (ref "U3") (pin "91") (pinfunction "PA03_91") (pintype "bidirectional"))
    )
    (net (code "14") (name "/PA04") (class "Default")
      (node (ref "R20") (pin "1") (pinfunction "1_1") (pintype "passive"))
      (node (ref "U3") (pin "77") (pinfunction "PA04_77") (pintype "bidirectional"))
    )
    (net (code "17") (name "/PA07_XIN32") (class "Default")
      (node (ref "C16") (pin "1") (pinfunction "1_1") (pintype "passive"))
      (node (ref "R280") (pin "1") (pinfunction "1_1") (pintype "passive"))
      (node (ref "U3") (pin "35") (pinfunction "PA07_35") (pintype "bidirectional"))
      (node (ref "Y5") (pin "2") (pinfunction "Osc2_2") (pintype "passive"))
    )
    (net (code "18") (name "/PA08_XOUT32") (class "Default")
      (node (ref "C17") (pin "1") (pinfunction "1_1") (pintype "passive"))
      (node (ref "R280") (pin "2") (pinfunction "2_2") (pintype "passive"))
      (node (ref "U3") (pin "36") (pinfunction "PA08_36") (pintype "bidirectional"))
      (node (ref "Y5") (pin "1") (pinfunction "Osc1_1") (pintype "passive"))
    )
    (net (code "19") (name "/PA09") (class "Default")
      (node (ref "R24") (pin "1") (pinfunction "1_1") (pintype "passive"))
      (node (ref "U3") (pin "75") (pinfunction "PA09_75") (pintype "bidirectional"))
    )
    (net (code "20") (name "/PA10") (class "Default")
      (node (ref "R26") (pin "1") (pinfunction "1_1") (pintype "passive"))
      (node (ref "U3") (pin "66") (pinfunction "PA10_66") (pintype "bidirectional"))
    )
    (net (code "21") (name "/PA11") (class "Default")
      (node (ref "R28") (pin "1") (pinfunction "1_1") (pintype "passive"))
      (node (ref "U3") (pin "64") (pinfunction "PA11_64") (pintype "bidirectional"))
    )
    (net (code "22") (name "/PA12") (class "Default")
      (node (ref "R30") (pin "1") (pinfunction "1_1") (pintype "passive"))
      (node (ref "U3") (pin "68") (pinfunction "PA12_68") (pintype "bidirectional"))
    )
    (net (code "23") (name "/PA13") (class "Default")
      (node (ref "R32") (pin "1") (pinfunction "1_1") (pintype "passive"))
      (node (ref "U3") (pin "42") (pinfunction "PA13_42") (pintype "bidirectional"))
    )
    (net (code "24") (name "/PA14") (class "Default")
      (node (ref "R34") (pin "1") (pinfunction "1_1") (pintype "passive"))
      (node (ref "U3") (pin "51") (pinfunction "PA14_51") (pintype "bidirectional"))
    )
    (net (code "25") (name "/PA15") (class "Default")
      (node (ref "R36") (pin "1") (pinfunction "1_1") (pintype "passive"))
      (node (ref "U3") (pin "49") (pinfunction "PA15_49") (pintype "bidirectional"))
    )
    (net (code "26") (name "/PA16") (class "Default")
      (node (ref "R37") (pin "1") (pinfunction "1_1") (pintype "passive"))
      (node (ref "U3") (pin "45") (pinfunction "PA16_45") (pintype "bidirectional"))
    )
    (net (code "27") (name "/PA17") (class "Default")
      (node (ref "R38") (pin "1") (pinfunction "1_1") (pintype "passive"))
      (node (ref "U3") (pin "25") (pinfunction "PA17_25") (pintype "bidirectional"))
    )
    (net (code "28") (name "/PA18") (class "Default")
      (node (ref "R151") (pin "1") (pinfunction "1_1") (pintype "passive"))
      (node (ref "U3") (pin "24") (pinfunction "PA18_24") (pintype "bidirectional"))
    )
    (net (code "29") (name "/PA19") (class "Default")
      (node (ref "C213") (pin "2") (pinfunction "2_2") (pintype "passive"))
      (node (ref "R143") (pin "1") (pinfunction "1_1") (pintype "passive"))
      (node (ref "U3") (pin "23") (pinfunction "PA19_23") (pintype "bidirectional"))
    )
    (net (code "30") (name "/PA20") (class "Default")
      (node (ref "C215") (pin "2") (pinfunction "2_2") (pintype "passive"))
      (node (ref "R150") (pin "1") (pinfunction "1_1") (pintype "passive"))
      (node (ref "U3") (pin "22") (pinfunction "PA20_22") (pintype "bidirectional"))
    )
    (net (code "31") (name "/PA22") (class "Default")
      (node (ref "R44") (pin "1") (pinfunction "1_1") (pintype "passive"))
      (node (ref "U3") (pin "37") (pinfunction "PA22_37") (pintype "bidirectional"))
    )
    (net (code "32") (name "/PA23") (class "Default")
      (node (ref "R46") (pin "1") (pinfunction "1_1") (pintype "passive"))
      (node (ref "U3") (pin "46") (pinfunction "PA23_46") (pintype "bidirectional"))
    )
    (net (code "33") (name "/PA24") (class "Default")
      (node (ref "R47") (pin "1") (pinfunction "1_1") (pintype "passive"))
      (node (ref "U3") (pin "56") (pinfunction "PA24_56") (pintype "bidirectional"))
    )
    (net (code "34") (name "/PA25") (class "Default")
      (node (ref "R48") (pin "1") (pinfunction "1_1") (pintype "passive"))
      (node (ref "U3") (pin "59") (pinfunction "PA25_59") (pintype "bidirectional"))
    )
    (net (code "35") (name "/PA26") (class "Default")
      (node (ref "R50") (pin "1") (pinfunction "1_1") (pintype "passive"))
      (node (ref "U3") (pin "62") (pinfunction "PA26_62") (pintype "bidirectional"))
    )
    (net (code "36") (name "/PA27") (class "Default")
      (node (ref "R52") (pin "1") (pinfunction "1_1") (pintype "passive"))
      (node (ref "U3") (pin "70") (pinfunction "PA27_70") (pintype "bidirectional"))
    )
    (net (code "37") (name "/PA28") (class "Default")
      (node (ref "R54") (pin "1") (pinfunction "1_1") (pintype "passive"))
      (node (ref "U3") (pin "112") (pinfunction "PA28_112") (pintype "bidirectional"))
    )
    (net (code "38") (name "/PA29") (class "Default")
      (node (ref "R56") (pin "1") (pinfunction "1_1") (pintype "passive"))
      (node (ref "U3") (pin "129") (pinfunction "PA29_129") (pintype "bidirectional"))
    )
    (net (code "39") (name "/PA30") (class "Default")
      (node (ref "R58") (pin "1") (pinfunction "1_1") (pintype "passive"))
      (node (ref "U3") (pin "116") (pinfunction "PA30_116") (pintype "bidirectional"))
    )
    (net (code "40") (name "/PA31") (class "Default")
      (node (ref "R59") (pin "1") (pinfunction "1_1") (pintype "passive"))
      (node (ref "U3") (pin "118") (pinfunction "PA31_118") (pintype "bidirectional"))
    )
    (net (code "41") (name "/PB00") (class "Default")
      (node (ref "C225") (pin "2") (pinfunction "2_2") (pintype "passive"))
      (node (ref "R73") (pin "2") (pinfunction "2_2") (pintype "passive"))
      (node (ref "U3") (pin "21") (pinfunction "PB00_21") (pintype "bidirectional"))
    )
    (net (code "42") (name "/PB01") (class "Default")
      (node (ref "C226") (pin "2") (pinfunction "2_2") (pintype "passive"))
      (node (ref "R75") (pin "2") (pinfunction "2_2") (pintype "passive"))
      (node (ref "U3") (pin "20") (pinfunction "PB01_20") (pintype "bidirectional"))
    )
    (net (code "43") (name "/PB02") (class "Default")
      (node (ref "C227") (pin "2") (pinfunction "2_2") (pintype "passive"))
      (node (ref "R77") (pin "2") (pinfunction "2_2") (pintype "passive"))
      (node (ref "U3") (pin "26") (pinfunction "PB02_26") (pintype "bidirectional"))
    )
    (net (code "44") (name "/PB03") (class "Default")
      (node (ref "C228") (pin "2") (pinfunction "2_2") (pintype "passive"))
      (node (ref "R79") (pin "2") (pinfunction "2_2") (pintype "passive"))
      (node (ref "U3") (pin "31") (pinfunction "PB03_31") (pintype "bidirectional"))
    )
    (net (code "45") (name "/PB04") (class "Default")
      (node (ref "R81") (pin "2") (pinfunction "2_2") (pintype "passive"))
      (node (ref "U3") (pin "105") (pinfunction "PB04_105") (pintype "bidirectional"))
    )
    (net (code "46") (name "/PB05") (class "Default")
      (node (ref "R83") (pin "2") (pinfunction "2_2") (pintype "passive"))
      (node (ref "R86") (pin "2") (pinfunction "2_2") (pintype "passive"))
      (node (ref "U3") (pin "109") (pinfunction "PB05_109") (pintype "bidirectional"))
    )
    (net (code "47") (name "/PB06") (class "Default")
      (node (ref "R85") (pin "2") (pinfunction "2_2") (pintype "passive"))
      (node (ref "U3") (pin "79") (pinfunction "PB06_79") (pintype "bidirectional"))
    )
    (net (code "48") (name "/PB07") (class "Default")
      (node (ref "R88") (pin "2") (pinfunction "2_2") (pintype "passive"))
      (node (ref "U3") (pin "89") (pinfunction "PB07_89") (pintype "bidirectional"))
    )
    (net (code "49") (name "/PB12") (class "Default")
      (node (ref "R94") (pin "2") (pinfunction "2_2") (pintype "passive"))
      (node (ref "U3") (pin "87") (pinfunction "PB12_87") (pintype "bidirectional"))
    )
    (net (code "50") (name "/PB13") (class "Default")
      (node (ref "R96") (pin "2") (pinfunction "2_2") (pintype "passive"))
      (node (ref "U3") (pin "144") (pinfunction "PB13_144") (pintype "bidirectional"))
    )
    (net (code "51") (name "/PC00") (class "Default")
      (node (ref "C217") (pin "2") (pinfunction "2_2") (pintype "passive"))
      (node (ref "R278") (pin "1") (pinfunction "1_1") (pintype "passive"))
      (node (ref "U3") (pin "11") (pinfunction "PC00_11") (pintype "bidirectional"))
    )
    (net (code "52") (name "/PC01") (class "Default")
      (node (ref "R64") (pin "1") (pinfunction "1_1") (pintype "passive"))
      (node (ref "U3") (pin "38") (pinfunction "PC01_38") (pintype "bidirectional"))
    )
    (net (code "53") (name "/PC02") (class "Default")
      (node (ref "R66") (pin "1") (pinfunction "1_1") (pintype "passive"))
      (node (ref "U3") (pin "39") (pinfunction "PC02_39") (pintype "bidirectional"))
    )
    (net (code "54") (name "/PC03") (class "Default")
      (node (ref "R68") (pin "1") (pinfunction "1_1") (pintype "passive"))
      (node (ref "U3") (pin "40") (pinfunction "PC03_40") (pintype "bidirectional"))
    )
    (net (code "55") (name "/PC04") (class "Default")
      (node (ref "R69") (pin "1") (pinfunction "1_1") (pintype "passive"))
      (node (ref "U3") (pin "41") (pinfunction "PC04_41") (pintype "bidirectional"))
    )
    (net (code "56") (name "/PC05") (class "Default")
      (node (ref "R70") (pin "1") (pinfunction "1_1") (pintype "passive"))
      (node (ref "U3") (pin "58") (pinfunction "PC05_58") (pintype "bidirectional"))
    )
    (net (code "57") (name "/PC06") (class "Default")
      (node (ref "R71") (pin "1") (pinfunction "1_1") (pintype "passive"))
      (node (ref "U3") (pin "54") (pinfunction "PC06_54") (pintype "bidirectional"))
    )
    (net (code "58") (name "/PC07") (class "Default")
      (node (ref "R72") (pin "1") (pinfunction "1_1") (pintype "passive"))
      (node (ref "U3") (pin "48") (pinfunction "PC07_48") (pintype "bidirectional"))
    )
    (net (code "59") (name "/PC08") (class "Default")
      (node (ref "R74") (pin "1") (pinfunction "1_1") (pintype "passive"))
      (node (ref "U3") (pin "82") (pinfunction "PC08_82") (pintype "bidirectional"))
    )
    (net (code "60") (name "/PC09") (class "Default")
      (node (ref "R76") (pin "1") (pinfunction "1_1") (pintype "passive"))
      (node (ref "U3") (pin "86") (pinfunction "PC09_86") (pintype "bidirectional"))
    )
    (net (code "61") (name "/PC10") (class "Default")
      (node (ref "R78") (pin "1") (pinfunction "1_1") (pintype "passive"))
      (node (ref "U3") (pin "90") (pinfunction "PC10_90") (pintype "bidirectional"))
    )
    (net (code "62") (name "/PC11") (class "Default")
      (node (ref "R80") (pin "1") (pinfunction "1_1") (pintype "passive"))
      (node (ref "U3") (pin "94") (pinfunction "PC11_94") (pintype "bidirectional"))
    )
    (net (code "63") (name "/PC12") (class "Default")
      (node (ref "R82") (pin "1") (pinfunction "1_1") (pintype "passive"))
      (node (ref "U3") (pin "17") (pinfunction "PC12_17") (pintype "bidirectional"))
    )
    (net (code "64") (name "/PC13") (class "Default")
      (node (ref "C218") (pin "2") (pinfunction "2_2") (pintype "passive"))
      (node (ref "R84") (pin "1") (pinfunction "1_1") (pintype "passive"))
      (node (ref "U3") (pin "19") (pinfunction "PC13_19") (pintype "bidirectional"))
    )
    (net (code "65") (name "/PC14") (class "Default")
      (node (ref "R87") (pin "1") (pinfunction "1_1") (pintype "passive"))
      (node (ref "U3") (pin "97") (pinfunction "PC14_97") (pintype "bidirectional"))
    )
    (net (code "66") (name "/PC15") (class "Default")
      (node (ref "C219") (pin "2") (pinfunction "2_2") (pintype "passive"))
      (node (ref "R89") (pin "1") (pinfunction "1_1") (pintype "passive"))
      (node (ref "U3") (pin "18") (pinfunction "PC15_18") (pintype "bidirectional"))
    )
    (net (code "67") (name "/PC16") (class "Default")
      (node (ref "R91") (pin "1") (pinfunction "1_1") (pintype "passive"))
      (node (ref "U3") (pin "100") (pinfunction "PC16_100") (pintype "bidirectional"))
    )
    (net (code "68") (name "/PC17") (class "Default")
      (node (ref "R93") (pin "1") (pinfunction "1_1") (pintype "passive"))
      (node (ref "U3") (pin "103") (pinfunction "PC17_103") (pintype "bidirectional"))
    )
    (net (code "69") (name "/PC18") (class "Default")
      (node (ref "R95") (pin "1") (pinfunction "1_1") (pintype "passive"))
      (node (ref "U3") (pin "111") (pinfunction "PC18_111") (pintype "bidirectional"))
    )
    (net (code "70") (name "/PC19") (class "Default")
      (node (ref "R97") (pin "1") (pinfunction "1_1") (pintype "passive"))
      (node (ref "U3") (pin "117") (pinfunction "PC19_117") (pintype "bidirectional"))
    )
    (net (code "71") (name "/PC20") (class "Default")
      (node (ref "R98") (pin "1") (pinfunction "1_1") (pintype "passive"))
      (node (ref "U3") (pin "120") (pinfunction "PC20_120") (pintype "bidirectional"))
    )
    (net (code "72") (name "/PC21") (class "Default")
      (node (ref "R99") (pin "1") (pinfunction "1_1") (pintype "passive"))
      (node (ref "U3") (pin "122") (pinfunction "PC21_122") (pintype "bidirectional"))
    )
    (net (code "73") (name "/PC22") (class "Default")
      (node (ref "R100") (pin "1") (pinfunction "1_1") (pintype "passive"))
      (node (ref "U3") (pin "124") (pinfunction "PC22_124") (pintype "bidirectional"))
    )
    (net (code "74") (name "/PC23") (class "Default")
      (node (ref "R101") (pin "1") (pinfunction "1_1") (pintype "passive"))
      (node (ref "U3") (pin "127") (pinfunction "PC23_127") (pintype "bidirectional"))
    )
    (net (code "75") (name "/PC24") (class "Default")
      (node (ref "R102") (pin "1") (pinfunction "1_1") (pintype "passive"))
      (node (ref "U3") (pin "130") (pinfunction "PC24_130") (pintype "bidirectional"))
    )
    (net (code "76") (name "/PC25") (class "Default")
      (node (ref "R286") (pin "1") (pinfunction "1_1") (pintype "passive"))
      (node (ref "U3") (pin "133") (pinfunction "PC25_133") (pintype "bidirectional"))
    )
    (net (code "77") (name "/PC26") (class "Default")
      (node (ref "R103") (pin "1") (pinfunction "1_1") (pintype "passive"))
      (node (ref "U3") (pin "13") (pinfunction "PC26_13") (pintype "bidirectional"))
    )
    (net (code "78") (name "/PC27") (class "Default")
      (node (ref "R104") (pin "1") (pinfunction "1_1") (pintype "passive"))
      (node (ref "U3") (pin "12") (pinfunction "PC27_12") (pintype "bidirectional"))
    )
    (net (code "79") (name "/PC28") (class "Default")
      (node (ref "R105") (pin "1") (pinfunction "1_1") (pintype "passive"))
      (node (ref "U3") (pin "76") (pinfunction "PC28_76") (pintype "bidirectional"))
    )
    (net (code "80") (name "/PC29") (class "Default")
      (node (ref "C220") (pin "2") (pinfunction "2_2") (pintype "passive"))
      (node (ref "R106") (pin "1") (pinfunction "1_1") (pintype "passive"))
      (node (ref "U3") (pin "16") (pinfunction "PC29_16") (pintype "bidirectional"))
    )
    (net (code "81") (name "/PC30") (class "Default")
      (node (ref "C221") (pin "2") (pinfunction "2_2") (pintype "passive"))
      (node (ref "R107") (pin "1") (pinfunction "1_1") (pintype "passive"))
      (node (ref "U3") (pin "15") (pinfunction "PC30_15") (pintype "bidirectional"))
    )
    (net (code "82") (name "/PC31") (class "Default")
      (node (ref "C223") (pin "2") (pinfunction "2_2") (pintype "passive"))
      (node (ref "R108") (pin "1") (pinfunction "1_1") (pintype "passive"))
      (node (ref "U3") (pin "14") (pinfunction "PC31_14") (pintype "bidirectional"))
    )
    (net (code "83") (name "/PD00") (class "Default")
      (node (ref "R12") (pin "2") (pinfunction "2_2") (pintype "passive"))
      (node (ref "U3") (pin "1") (pinfunction "PD00_1") (pintype "bidirectional"))
    )
    (net (code "84") (name "/PD01") (class "Default")
      (node (ref "R14") (pin "2") (pinfunction "2_2") (pintype "passive"))
      (node (ref "U3") (pin "132") (pinfunction "PD01_132") (pintype "bidirectional"))
    )
    (net (code "85") (name "/PD02") (class "Default")
      (node (ref "R16") (pin "2") (pinfunction "2_2") (pintype "passive"))
      (node (ref "U3") (pin "131") (pinfunction "PD02_131") (pintype "bidirectional"))
    )
    (net (code "86") (name "/PD03") (class "Default")
      (node (ref "R18") (pin "2") (pinfunction "2_2") (pintype "passive"))
      (node (ref "U3") (pin "128") (pinfunction "PD03_128") (pintype "bidirectional"))
    )
    (net (code "87") (name "/PD04") (class "Default")
      (node (ref "R19") (pin "2") (pinfunction "2_2") (pintype "passive"))
      (node (ref "U3") (pin "126") (pinfunction "PD04_126") (pintype "bidirectional"))
    )
    (net (code "88") (name "/PD05") (class "Default")
      (node (ref "R21") (pin "2") (pinfunction "2_2") (pintype "passive"))
      (node (ref "U3") (pin "125") (pinfunction "PD05_125") (pintype "bidirectional"))
    )
    (net (code "89") (name "/PD06") (class "Default")
      (node (ref "R23") (pin "2") (pinfunction "2_2") (pintype "passive"))
      (node (ref "U3") (pin "121") (pinfunction "PD06_121") (pintype "bidirectional"))
    )
    (net (code "90") (name "/PD07") (class "Default")
      (node (ref "R22") (pin "2") (pinfunction "2_2") (pintype "passive"))
      (node (ref "U3") (pin "119") (pinfunction "PD07_119") (pintype "bidirectional"))
    )
    (net (code "91") (name "/PD08") (class "Default")
      (node (ref "R312") (pin "2") (pinfunction "2_2") (pintype "passive"))
      (node (ref "U3") (pin "113") (pinfunction "PD08_113") (pintype "bidirectional"))
    )
    (net (code "92") (name "/PD09") (class "Default")
      (node (ref "R25") (pin "2") (pinfunction "2_2") (pintype "passive"))
      (node (ref "U3") (pin "110") (pinfunction "PD09_110") (pintype "bidirectional"))
    )
    (net (code "93") (name "/PD10") (class "Default")
      (node (ref "R27") (pin "2") (pinfunction "2_2") (pintype "passive"))
      (node (ref "U3") (pin "101") (pinfunction "PD10_101") (pintype "bidirectional"))
    )
    (net (code "94") (name "/PD11") (class "Default")
      (node (ref "R29") (pin "2") (pinfunction "2_2") (pintype "passive"))
      (node (ref "U3") (pin "98") (pinfunction "PD11_98") (pintype "bidirectional"))
    )
    (net (code "95") (name "/PD12") (class "Default")
      (node (ref "R31") (pin "2") (pinfunction "2_2") (pintype "passive"))
      (node (ref "U3") (pin "92") (pinfunction "PD12_92") (pintype "bidirectional"))
    )
    (net (code "96") (name "/PD13") (class "Default")
      (node (ref "R33") (pin "2") (pinfunction "2_2") (pintype "passive"))
      (node (ref "U3") (pin "88") (pinfunction "PD13_88") (pintype "bidirectional"))
    )
    (net (code "97") (name "/PD14") (class "Default")
      (node (ref "R35") (pin "2") (pinfunction "2_2") (pintype "passive"))
      (node (ref "U3") (pin "84") (pinfunction "PD14_84") (pintype "bidirectional"))
    )
    (net (code "98") (name "/PD15") (class "Default")
      (node (ref "R131") (pin "2") (pinfunction "2_2") (pintype "passive"))
      (node (ref "U3") (pin "106") (pinfunction "PD15_106") (pintype "bidirectional"))
    )
    (net (code "99") (name "/PD16") (class "Default")
      (node (ref "R133") (pin "2") (pinfunction "2_2") (pintype "passive"))
      (node (ref "U3") (pin "78") (pinfunction "PD16_78") (pintype "bidirectional"))
    )
    (net (code "100") (name "/PD17") (class "Default")
      (node (ref "R39") (pin "2") (pinfunction "2_2") (pintype "passive"))
      (node (ref "U3") (pin "74") (pinfunction "PD17_74") (pintype "bidirectional"))
    )
    (net (code "101") (name "/PD18") (class "Default")
      (node (ref "R40") (pin "2") (pinfunction "2_2") (pintype "passive"))
      (node (ref "U3") (pin "69") (pinfunction "PD18_69") (pintype "bidirectional"))
    )
    (net (code "102") (name "/PD19") (class "Default")
      (node (ref "R41") (pin "1") (pinfunction "1_1") (pintype "passive"))
      (node (ref "U3") (pin "67") (pinfunction "PD19_67") (pintype "bidirectional"))
    )
    (net (code "103") (name "/PD20") (class "Default")
      (node (ref "R42") (pin "2") (pinfunction "2_2") (pintype "passive"))
      (node (ref "U3") (pin "65") (pinfunction "PD20_65") (pintype "bidirectional"))
    )
    (net (code "104") (name "/PD21") (class "Default")
      (node (ref "R43") (pin "2") (pinfunction "2_2") (pintype "passive"))
      (node (ref "U3") (pin "63") (pinfunction "PD21_63") (pintype "bidirectional"))
    )
    (net (code "105") (name "/PD22") (class "Default")
      (node (ref "R45") (pin "2") (pinfunction "2_2") (pintype "passive"))
      (node (ref "U3") (pin "60") (pinfunction "PD22_60") (pintype "bidirectional"))
    )
    (net (code "106") (name "/PD23") (class "Default")
      (node (ref "R126") (pin "2") (pinfunction "2_2") (pintype "passive"))
      (node (ref "U3") (pin "57") (pinfunction "PD23_57") (pintype "bidirectional"))
    )
    (net (code "107") (name "/PD24") (class "Default")
      (node (ref "R127") (pin "2") (pinfunction "2_2") (pintype "passive"))
      (node (ref "U3") (pin "55") (pinfunction "PD24_55") (pintype "bidirectional"))
    )
    (net (code "108") (name "/PD25") (class "Default")
      (node (ref "R49") (pin "2") (pinfunction "2_2") (pintype "passive"))
      (node (ref "U3") (pin "52") (pinfunction "PD25_52") (pintype "bidirectional"))
    )
    (net (code "109") (name "/PD26") (class "Default")
      (node (ref "R51") (pin "2") (pinfunction "2_2") (pintype "passive"))
      (node (ref "U3") (pin "53") (pinfunction "PD26_53") (pintype "bidirectional"))
    )
    (net (code "110") (name "/PD27") (class "Default")
      (node (ref "R53") (pin "2") (pinfunction "2_2") (pintype "passive"))
      (node (ref "U3") (pin "47") (pinfunction "PD27_47") (pintype "bidirectional"))
    )
    (net (code "111") (name "/PD28") (class "Default")
      (node (ref "R55") (pin "2") (pinfunction "2_2") (pintype "passive"))
      (node (ref "U3") (pin "71") (pinfunction "PD28_71") (pintype "bidirectional"))
    )
    (net (code "112") (name "/PD29") (class "Default")
      (node (ref "R57") (pin "1") (pinfunction "1_1") (pintype "passive"))
      (node (ref "U3") (pin "108") (pinfunction "PD29_108") (pintype "bidirectional"))
    )
    (net (code "113") (name "/PD30") (class "Default")
      (node (ref "R277") (pin "1") (pinfunction "1_1") (pintype "passive"))
      (node (ref "U3") (pin "34") (pinfunction "PD30_34") (pintype "bidirectional"))
    )
    (net (code "114") (name "/PD31") (class "Default")
      (node (ref "R60") (pin "2") (pinfunction "2_2") (pintype "passive"))
      (node (ref "U3") (pin "2") (pinfunction "PD31_2") (pintype "bidirectional"))
    )
    (net (code "115") (name "/PE00") (class "Default")
      (node (ref "R279") (pin "2") (pinfunction "2_2") (pintype "passive"))
      (node (ref "U3") (pin "4") (pinfunction "PE00_4") (pintype "bidirectional"))
    )
    (net (code "116") (name "/PE01") (class "Default")
      (node (ref "R65") (pin "2") (pinfunction "2_2") (pintype "passive"))
      (node (ref "U3") (pin "6") (pinfunction "PE01_6") (pintype "bidirectional"))
    )
    (net (code "117") (name "/PE02") (class "Default")
      (node (ref "R67") (pin "2") (pinfunction "2_2") (pintype "passive"))
      (node (ref "U3") (pin "7") (pinfunction "PE02_7") (pintype "bidirectional"))
    )
    (net (code "118") (name "/PE03") (class "Default")
      (node (ref "R281") (pin "2") (pinfunction "2_2") (pintype "passive"))
      (node (ref "U3") (pin "10") (pinfunction "PE03_10") (pintype "bidirectional"))
    )
    (net (code "119") (name "/PE04") (class "Default")
      (node (ref "R282") (pin "2") (pinfunction "2_2") (pintype "passive"))
      (node (ref "U3") (pin "27") (pinfunction "PE04_27") (pintype "bidirectional"))
    )
    (net (code "120") (name "/PE05") (class "Default")
      (node (ref "R283") (pin "2") (pinfunction "2_2") (pintype "passive"))
      (node (ref "U3") (pin "28") (pinfunction "PE05_28") (pintype "bidirectional"))
    )
    (net (code "121") (name "/nSTART") (class "Default")
      (node (ref "R286") (pin "2") (pinfunction "2_2") (pintype "passive"))
    )
    (net (code "122") (name "3.3V_MCU") (class "Default")
      (node (ref "C21") (pin "1") (pinfunction "1_1") (pintype "passive"))
      (node (ref "C23") (pin "2") (pinfunction "2_2") (pintype "passive"))
      (node (ref "C24") (pin "2") (pinfunction "2_2") (pintype "passive"))
      (node (ref "C25") (pin "2") (pinfunction "2_2") (pintype "passive"))
      (node (ref "C26") (pin "2") (pinfunction "2_2") (pintype "passive"))
      (node (ref "C27") (pin "2") (pinfunction "2_2") (pintype "passive"))
      (node (ref "C28") (pin "2") (pinfunction "2_2") (pintype "passive"))
      (node (ref "C29") (pin "2") (pinfunction "2_2") (pintype "passive"))
      (node (ref "C30") (pin "2") (pinfunction "2_2") (pintype "passive"))
      (node (ref "C31") (pin "2") (pinfunction "2_2") (pintype "passive"))
      (node (ref "J3") (pin "2") (pinfunction "2_2") (pintype "passive"))
      (node (ref "R141") (pin "1") (pinfunction "1_1") (pintype "passive"))
      (node (ref "R285") (pin "1") (pinfunction "1_1") (pintype "passive"))
      (node (ref "R61") (pin "2") (pinfunction "2_2") (pintype "passive"))
      (node (ref "U3") (pin "134") (pinfunction "VDDUTMII_134") (pintype "power_in"))
      (node (ref "U3") (pin "143") (pinfunction "VDDPLLUSB_143") (pintype "power_in"))
      (node (ref "U3") (pin "30") (pinfunction "VDDIO_30") (pintype "power_in"))
      (node (ref "U3") (pin "43") (pinfunction "VDDIO_43") (pintype "power_in"))
      (node (ref "U3") (pin "5") (pinfunction "VDDIN_5") (pintype "power_in"))
      (node (ref "U3") (pin "72") (pinfunction "VDDIO_72") (pintype "power_in"))
      (node (ref "U3") (pin "80") (pinfunction "VDDIO_80") (pintype "power_in"))
      (node (ref "U3") (pin "9") (pinfunction "ADVREFP_9") (pintype "power_in"))
      (node (ref "U3") (pin "96") (pinfunction "VDDIO_96") (pintype "power_in"))
    )
    (net (code "123") (name "ADC_SWITCH") (class "Default")
      (node (ref "R79") (pin "1") (pinfunction "1_1") (pintype "passive"))
    )
    (net (code "124") (name "ADC_TEMP1") (class "Default")
      (node (ref "R143") (pin "2") (pinfunction "2_2") (pintype "passive"))
    )
    (net (code "125") (name "ADC_TEMP2") (class "Default")
      (node (ref "R150") (pin "2") (pinfunction "2_2") (pintype "passive"))
    )
    (net (code "126") (name "ADC_TEMP3") (class "Default")
      (node (ref "R73") (pin "1") (pinfunction "1_1") (pintype "passive"))
    )
    (net (code "127") (name "ADC_TEMP4") (class "Default")
      (node (ref "R75") (pin "1") (pinfunction "1_1") (pintype "passive"))
    )
    (net (code "128") (name "ADC_TEMP5") (class "Default")
      (node (ref "R89") (pin "2") (pinfunction "2_2") (pintype "passive"))
    )
    (net (code "129") (name "ADC_TEMP6") (class "Default")
      (node (ref "R84") (pin "2") (pinfunction "2_2") (pintype "passive"))
    )
    (net (code "130") (name "ADC_TEMP7") (class "Default")
      (node (ref "R77") (pin "1") (pinfunction "1_1") (pintype "passive"))
    )
    (net (code "131") (name "ADC_TEMP8") (class "Default")
      (node (ref "R106") (pin "2") (pinfunction "2_2") (pintype "passive"))
    )
    (net (code "132") (name "ADC_TEMP_SENSOR") (class "Default")
      (node (ref "R107") (pin "2") (pinfunction "2_2") (pintype "passive"))
    )
    (net (code "133") (name "ADT2_USB_D_N") (class "Default")
      (node (ref "U3") (pin "136") (pinfunction "HSDM_136") (pintype "bidirectional"))
    )
    (net (code "134") (name "ADT2_USB_D_P") (class "Default")
      (node (ref "U3") (pin "137") (pinfunction "HSDP_137") (pintype "bidirectional"))
    )
    (net (code "135") (name "BMP390_INT") (class "Default")
      (node (ref "R14") (pin "1") (pinfunction "1_1") (pintype "passive"))
    )
    (net (code "136") (name "CANRX1") (class "Default")
      (node (ref "R82") (pin "2") (pinfunction "2_2") (pintype "passive"))
    )
    (net (code "137") (name "CANTX1") (class "Default")
      (node (ref "R87") (pin "2") (pinfunction "2_2") (pintype "passive"))
    )
    (net (code "138") (name "GND") (class "Default")
      (node (ref "C15") (pin "1") (pinfunction "1_1") (pintype "passive"))
      (node (ref "C16") (pin "2") (pinfunction "2_2") (pintype "passive"))
      (node (ref "C17") (pin "2") (pinfunction "2_2") (pintype "passive"))
      (node (ref "C18") (pin "1") (pinfunction "1_1") (pintype "passive"))
      (node (ref "C19") (pin "1") (pinfunction "1_1") (pintype "passive"))
      (node (ref "C20") (pin "1") (pinfunction "1_1") (pintype "passive"))
      (node (ref "C21") (pin "2") (pinfunction "2_2") (pintype "passive"))
      (node (ref "C213") (pin "1") (pinfunction "1_1") (pintype "passive"))
      (node (ref "C215") (pin "1") (pinfunction "1_1") (pintype "passive"))
      (node (ref "C217") (pin "1") (pinfunction "1_1") (pintype "passive"))
      (node (ref "C218") (pin "1") (pinfunction "1_1") (pintype "passive"))
      (node (ref "C219") (pin "1") (pinfunction "1_1") (pintype "passive"))
      (node (ref "C22") (pin "2") (pinfunction "2_2") (pintype "passive"))
      (node (ref "C220") (pin "1") (pinfunction "1_1") (pintype "passive"))
      (node (ref "C221") (pin "1") (pinfunction "1_1") (pintype "passive"))
      (node (ref "C223") (pin "1") (pinfunction "1_1") (pintype "passive"))
      (node (ref "C225") (pin "1") (pinfunction "1_1") (pintype "passive"))
      (node (ref "C226") (pin "1") (pinfunction "1_1") (pintype "passive"))
      (node (ref "C227") (pin "1") (pinfunction "1_1") (pintype "passive"))
      (node (ref "C228") (pin "1") (pinfunction "1_1") (pintype "passive"))
      (node (ref "C23") (pin "1") (pinfunction "1_1") (pintype "passive"))
      (node (ref "C24") (pin "1") (pinfunction "1_1") (pintype "passive"))
      (node (ref "C25") (pin "1") (pinfunction "1_1") (pintype "passive"))
      (node (ref "C26") (pin "1") (pinfunction "1_1") (pintype "passive"))
      (node (ref "C27") (pin "1") (pinfunction "1_1") (pintype "passive"))
      (node (ref "C28") (pin "1") (pinfunction "1_1") (pintype "passive"))
      (node (ref "C29") (pin "1") (pinfunction "1_1") (pintype "passive"))
      (node (ref "C30") (pin "1") (pinfunction "1_1") (pintype "passive"))
      (node (ref "C31") (pin "1") (pinfunction "1_1") (pintype "passive"))
      (node (ref "C32") (pin "1") (pinfunction "1_1") (pintype "passive"))
      (node (ref "C33") (pin "1") (pinfunction "1_1") (pintype "passive"))
      (node (ref "C34") (pin "1") (pinfunction "1_1") (pintype "passive"))
      (node (ref "C35") (pin "1") (pinfunction "1_1") (pintype "passive"))
      (node (ref "C36") (pin "1") (pinfunction "1_1") (pintype "passive"))
      (node (ref "C37") (pin "1") (pinfunction "1_1") (pintype "passive"))
      (node (ref "C38") (pin "1") (pinfunction "1_1") (pintype "passive"))
      (node (ref "C39") (pin "1") (pinfunction "1_1") (pintype "passive"))
      (node (ref "J3") (pin "3") (pinfunction "3_3") (pintype "passive"))
      (node (ref "R110") (pin "1") (pinfunction "1_1") (pintype "passive"))
      (node (ref "R298") (pin "2") (pinfunction "2_2") (pintype "passive"))
      (node (ref "U3") (pin "115") (pinfunction "GND_115") (pintype "power_in"))
      (node (ref "U3") (pin "135") (pinfunction "GND_135") (pintype "power_in"))
      (node (ref "U3") (pin "138") (pinfunction "GND_138") (pintype "power_in"))
      (node (ref "U3") (pin "44") (pinfunction "GND_44") (pintype "power_in"))
      (node (ref "U3") (pin "61") (pinfunction "GND_61") (pintype "power_in"))
      (node (ref "U3") (pin "8") (pinfunction "ADVREFN_8") (pintype "power_in"))
      (node (ref "U3") (pin "95") (pinfunction "GND_95") (pintype "power_in"))
      (node (ref "XC2") (pin "2") (pinfunction "2_2") (pintype "passive"))
      (node (ref "XC2") (pin "4") (pinfunction "4_4") (pintype "passive"))
    )
    (net (code "139") (name "HEATER_PWM_1") (class "Default")
      (node (ref "R52") (pin "2") (pinfunction "2_2") (pintype "passive"))
    )
    (net (code "140") (name "HEATER_PWM_2") (class "Default")
      (node (ref "R11") (pin "2") (pinfunction "2_2") (pintype "passive"))
    )
    (net (code "141") (name "HEATER_PWM_3") (class "Default")
      (node (ref "R13") (pin "2") (pinfunction "2_2") (pintype "passive"))
    )
    (net (code "142") (name "HEATER_PWM_4") (class "Default")
      (node (ref "R50") (pin "2") (pinfunction "2_2") (pintype "passive"))
    )
    (net (code "143") (name "HEATER_PWM_5") (class "Default")
      (node (ref "R74") (pin "2") (pinfunction "2_2") (pintype "passive"))
    )
    (net (code "144") (name "HEATER_PWM_6") (class "Default")
      (node (ref "R101") (pin "2") (pinfunction "2_2") (pintype "passive"))
    )
    (net (code "145") (name "HEATER_PWM_7") (class "Default")
      (node (ref "R70") (pin "2") (pinfunction "2_2") (pintype "passive"))
    )
    (net (code "146") (name "HEATER_PWM_8") (class "Default")
      (node (ref "R71") (pin "2") (pinfunction "2_2") (pintype "passive"))
    )
    (net (code "147") (name "IF_MCU_SHUTDOWN") (class "Default")
      (node (ref "R312") (pin "1") (pinfunction "1_1") (pintype "passive"))
    )
    (net (code "148") (name "LASER_ADC_1") (class "Default")
      (node (ref "R108") (pin "2") (pinfunction "2_2") (pintype "passive"))
    )
    (net (code "149") (name "LASER_ADC_2") (class "Default")
      (node (ref "R278") (pin "2") (pinfunction "2_2") (pintype "passive"))
    )
    (net (code "151") (name "LASER_DAC_LATCH") (class "Default")
      (node (ref "R91") (pin "2") (pinfunction "2_2") (pintype "passive"))
    )
    (net (code "152") (name "LASER_SPI_nCS1") (class "Default")
      (node (ref "R59") (pin "2") (pinfunction "2_2") (pintype "passive"))
    )
    (net (code "153") (name "LASER_SW_EXT_CS") (class "Default")
      (node (ref "R37") (pin "2") (pinfunction "2_2") (pintype "passive"))
    )
    (net (code "154") (name "LASER_SW_INT_CS") (class "Default")
      (node (ref "R72") (pin "2") (pinfunction "2_2") (pintype "passive"))
    )
    (net (code "155") (name "LSM6DSOX_INT") (class "Default")
      (node (ref "R99") (pin "2") (pinfunction "2_2") (pintype "passive"))
    )
    (net (code "156") (name "MCU_CONSOLE_RX") (class "Default")
      (node (ref "R49") (pin "1") (pinfunction "1_1") (pintype "passive"))
    )
    (net (code "157") (name "MCU_CONSOLE_TX") (class "Default")
      (node (ref "R51") (pin "1") (pinfunction "1_1") (pintype "passive"))
    )
    (net (code "158") (name "MCU_FRAM_nCS") (class "Default")
      (node (ref "R41") (pin "2") (pinfunction "2_2") (pintype "passive"))
    )
    (net (code "159") (name "MCU_HD4_I2C2_SCL") (class "Default")
      (node (ref "R55") (pin "1") (pinfunction "1_1") (pintype "passive"))
    )
    (net (code "160") (name "MCU_HD4_I2C2_SDA") (class "Default")
      (node (ref "R53") (pin "1") (pinfunction "1_1") (pintype "passive"))
    )
    (net (code "161") (name "MCU_HD4_I2C_EN") (class "Default")
      (node (ref "R93") (pin "2") (pinfunction "2_2") (pintype "passive"))
    )
    (net (code "162") (name "MCU_I2C0_SCL") (class "Default")
      (node (ref "R20") (pin "2") (pinfunction "2_2") (pintype "passive"))
    )
    (net (code "163") (name "MCU_I2C0_SDA") (class "Default")
      (node (ref "R17") (pin "2") (pinfunction "2_2") (pintype "passive"))
    )
    (net (code "164") (name "MCU_I2C1_SCL") (class "Default")
      (node (ref "R86") (pin "1") (pinfunction "1_1") (pintype "passive"))
    )
    (net (code "165") (name "MCU_I2C1_SDA") (class "Default")
      (node (ref "R81") (pin "1") (pinfunction "1_1") (pintype "passive"))
    )
    (net (code "166") (name "MCU_MPD_DAC") (class "Default")
      (node (ref "R96") (pin "1") (pinfunction "1_1") (pintype "passive"))
    )
    (net (code "167") (name "MCU_MPD_EN") (class "Default")
      (node (ref "R22") (pin "1") (pinfunction "1_1") (pintype "passive"))
    )
    (net (code "168") (name "MCU_MPD_PWM") (class "Default")
      (node (ref "R279") (pin "1") (pinfunction "1_1") (pintype "passive"))
    )
    (net (code "169") (name "MCU_MRAM_QSPI_CLK") (class "Default")
      (node (ref "R34") (pin "2") (pinfunction "2_2") (pintype "passive"))
    )
    (net (code "170") (name "MCU_MRAM_QSPI_IO0") (class "Default")
      (node (ref "R32") (pin "2") (pinfunction "2_2") (pintype "passive"))
    )
    (net (code "171") (name "MCU_MRAM_QSPI_IO1") (class "Default")
      (node (ref "R30") (pin "2") (pinfunction "2_2") (pintype "passive"))
    )
    (net (code "172") (name "MCU_MRAM_QSPI_IO2") (class "Default")
      (node (ref "R38") (pin "2") (pinfunction "2_2") (pintype "passive"))
    )
    (net (code "173") (name "MCU_MRAM_QSPI_IO3") (class "Default")
      (node (ref "R60") (pin "1") (pinfunction "1_1") (pintype "passive"))
    )
    (net (code "174") (name "MCU_PRAM_SPI1_nCS") (class "Default")
      (node (ref "R105") (pin "2") (pinfunction "2_2") (pintype "passive"))
    )
    (net (code "175") (name "MCU_PRAM_SW_nEN") (class "Default")
      (node (ref "R35") (pin "1") (pinfunction "1_1") (pintype "passive"))
    )
    (net (code "176") (name "MCU_RAM_QSPI_nCS") (class "Default")
      (node (ref "R28") (pin "2") (pinfunction "2_2") (pintype "passive"))
    )
    (net (code "177") (name "MCU_RTC_CLKOUT") (class "Default")
      (node (ref "R68") (pin "2") (pinfunction "2_2") (pintype "passive"))
    )
    (net (code "178") (name "MCU_RTC_INT") (class "Default")
      (node (ref "R69") (pin "2") (pinfunction "2_2") (pintype "passive"))
    )
    (net (code "179") (name "MCU_SENSOR1_nIRQ") (class "Default")
      (node (ref "R126") (pin "1") (pinfunction "1_1") (pintype "passive"))
    )
    (net (code "180") (name "MCU_SENSOR2_nIRQ") (class "Default")
      (node (ref "R127") (pin "1") (pinfunction "1_1") (pintype "passive"))
    )
    (net (code "181") (name "MCU_SENSOR3_nIRQ") (class "Default")
      (node (ref "R57") (pin "2") (pinfunction "2_2") (pintype "passive"))
    )
    (net (code "182") (name "MCU_SENSOR4_nIRQ") (class "Default")
      (node (ref "R277") (pin "2") (pinfunction "2_2") (pintype "passive"))
    )
    (net (code "183") (name "MCU_SOL_1_IN1") (class "Default")
      (node (ref "R15") (pin "2") (pinfunction "2_2") (pintype "passive"))
    )
    (net (code "184") (name "MCU_SOL_1_IN2") (class "Default")
      (node (ref "R97") (pin "2") (pinfunction "2_2") (pintype "passive"))
    )
    (net (code "185") (name "MCU_SOL_2_IN1") (class "Default")
      (node (ref "R40") (pin "1") (pinfunction "1_1") (pintype "passive"))
    )
    (net (code "186") (name "MCU_SOL_2_IN2") (class "Default")
      (node (ref "R283") (pin "1") (pinfunction "1_1") (pintype "passive"))
    )
    (net (code "187") (name "MCU_SOL_3_IN1") (class "Default")
      (node (ref "R46") (pin "2") (pinfunction "2_2") (pintype "passive"))
    )
    (net (code "188") (name "MCU_SOL_3_IN2") (class "Default")
      (node (ref "R44") (pin "2") (pinfunction "2_2") (pintype "passive"))
    )
    (net (code "189") (name "MCU_SOL_4_IN1") (class "Default")
      (node (ref "R48") (pin "2") (pinfunction "2_2") (pintype "passive"))
    )
    (net (code "190") (name "MCU_SOL_4_IN2") (class "Default")
      (node (ref "R47") (pin "2") (pinfunction "2_2") (pintype "passive"))
    )
    (net (code "191") (name "MCU_SOM_GPIO_A") (class "Default")
      (node (ref "R25") (pin "1") (pinfunction "1_1") (pintype "passive"))
    )
    (net (code "192") (name "MCU_SOM_GPIO_B") (class "Default")
      (node (ref "R27") (pin "1") (pinfunction "1_1") (pintype "passive"))
    )
    (net (code "193") (name "MCU_SPI0_MISO") (class "Default")
      (node (ref "R141") (pin "2") (pinfunction "2_2") (pintype "passive"))
      (node (ref "R42") (pin "1") (pinfunction "1_1") (pintype "passive"))
    )
    (net (code "194") (name "MCU_SPI0_MOSI") (class "Default")
      (node (ref "R43") (pin "1") (pinfunction "1_1") (pintype "passive"))
    )
    (net (code "195") (name "MCU_SPI0_SCK") (class "Default")
      (node (ref "R45") (pin "1") (pinfunction "1_1") (pintype "passive"))
    )
    (net (code "196") (name "MCU_SPI1_MISO") (class "Default")
      (node (ref "R103") (pin "2") (pinfunction "2_2") (pintype "passive"))
      (node (ref "R285") (pin "2") (pinfunction "2_2") (pintype "passive"))
    )
    (net (code "197") (name "MCU_SPI1_MOSI") (class "Default")
      (node (ref "R104") (pin "2") (pinfunction "2_2") (pintype "passive"))
    )
    (net (code "198") (name "MCU_SPI1_SCK") (class "Default")
      (node (ref "R102") (pin "2") (pinfunction "2_2") (pintype "passive"))
    )
    (net (code "199") (name "MCU_STATUS_LED_1") (class "Default")
      (node (ref "D36") (pin "2") (pinfunction "A_2") (pintype "passive"))
      (node (ref "R94") (pin "1") (pinfunction "1_1") (pintype "passive"))
    )
    (net (code "200") (name "MCU_UART0_RX_SOM_TX") (class "Default")
      (node (ref "R24") (pin "2") (pinfunction "2_2") (pintype "passive"))
    )
    (net (code "201") (name "MCU_UART0_TX_SOM_RX") (class "Default")
      (node (ref "R26") (pin "2") (pinfunction "2_2") (pintype "passive"))
    )
    (net (code "202") (name "MCU_USART_RXD2") (class "Default")
      (node (ref "R131") (pin "1") (pinfunction "1_1") (pintype "passive"))
    )
    (net (code "203") (name "MCU_USART_SCK2") (class "Default")
      (node (ref "R39") (pin "1") (pinfunction "1_1") (pintype "passive"))
    )
    (net (code "204") (name "MCU_USART_TXD2") (class "Default")
      (node (ref "R133") (pin "1") (pinfunction "1_1") (pintype "passive"))
    )
    (net (code "205") (name "MCU_WD_DONE") (class "Default")
      (node (ref "R65") (pin "1") (pinfunction "1_1") (pintype "passive"))
    )
    (net (code "206") (name "MCU_WD_WAKE") (class "Default")
      (node (ref "R67") (pin "1") (pinfunction "1_1") (pintype "passive"))
    )
    (net (code "207") (name "MCU_WD_nRESET") (class "Default")
      (node (ref "R62") (pin "2") (pinfunction "2_2") (pintype "passive"))
    )
    (net (code "208") (name "Net-(C15-Pad2)") (class "Default")
      (node (ref "C15") (pin "2") (pinfunction "2_2") (pintype "passive"))
      (node (ref "R61") (pin "1") (pinfunction "1_1") (pintype "passive"))
      (node (ref "R62") (pin "1") (pinfunction "1_1") (pintype "passive"))
      (node (ref "R63") (pin "2") (pinfunction "2_2") (pintype "passive"))
    )
    (net (code "209") (name "Net-(D36-K)") (class "Default")
      (node (ref "D36") (pin "1") (pinfunction "K_1") (pintype "passive"))
      (node (ref "R298") (pin "1") (pinfunction "1_1") (pintype "passive"))
    )
    (net (code "210") (name "Net-(U3-VBG)") (class "Default")
      (node (ref "C18") (pin "2") (pinfunction "2_2") (pintype "passive"))
      (node (ref "R110") (pin "2") (pinfunction "2_2") (pintype "passive"))
      (node (ref "U3") (pin "140") (pinfunction "VBG_140") (pintype "power_in"))
    )
    (net (code "211") (name "PHOTO_ADC_CONV") (class "Default")
      (node (ref "R36") (pin "2") (pinfunction "2_2") (pintype "passive"))
    )
    (net (code "212") (name "PHOTO_ADC_CS") (class "Default")
      (node (ref "R12") (pin "1") (pinfunction "1_1") (pintype "passive"))
    )
    (net (code "213") (name "PHOTO_ADC_EOC") (class "Default")
      (node (ref "R151") (pin "2") (pinfunction "2_2") (pintype "passive"))
    )
    (net (code "215") (name "PHOTO_SPI0_nCS2") (class "Default")
      (node (ref "R31") (pin "1") (pinfunction "1_1") (pintype "passive"))
    )
    (net (code "217") (name "POW_ONOFF_BUCK_PERI") (class "Default")
      (node (ref "R282") (pin "1") (pinfunction "1_1") (pintype "passive"))
    )
    (net (code "218") (name "POW_ONOFF_HD4") (class "Default")
      (node (ref "R18") (pin "1") (pinfunction "1_1") (pintype "passive"))
    )
    (net (code "219") (name "POW_ONOFF_HEATER") (class "Default")
      (node (ref "R281") (pin "1") (pinfunction "1_1") (pintype "passive"))
    )
    (net (code "220") (name "POW_ONOFF_LP") (class "Default")
      (node (ref "R23") (pin "1") (pinfunction "1_1") (pintype "passive"))
    )
    (net (code "223") (name "POW_ONOFF_SOM") (class "Default")
      (node (ref "R21") (pin "1") (pinfunction "1_1") (pintype "passive"))
    )
    (net (code "224") (name "POW_ONOFF_Solenoid") (class "Default")
      (node (ref "R16") (pin "1") (pinfunction "1_1") (pintype "passive"))
    )
    (net (code "225") (name "POW_ONOFF_TEC") (class "Default")
      (node (ref "R19") (pin "1") (pinfunction "1_1") (pintype "passive"))
    )
    (net (code "226") (name "SENSOR1_EN") (class "Default")
      (node (ref "R76") (pin "2") (pinfunction "2_2") (pintype "passive"))
    )
    (net (code "227") (name "SENSOR2_EN") (class "Default")
      (node (ref "R78") (pin "2") (pinfunction "2_2") (pintype "passive"))
    )
    (net (code "228") (name "SENSOR3_EN") (class "Default")
      (node (ref "R54") (pin "2") (pinfunction "2_2") (pintype "passive"))
    )
    (net (code "229") (name "SENSOR4_EN") (class "Default")
      (node (ref "R56") (pin "2") (pinfunction "2_2") (pintype "passive"))
    )
    (net (code "230") (name "SENSOR5_EN") (class "Default")
      (node (ref "R80") (pin "2") (pinfunction "2_2") (pintype "passive"))
    )
    (net (code "231") (name "TEC_SWEN_1") (class "Default")
      (node (ref "R58") (pin "2") (pinfunction "2_2") (pintype "passive"))
    )
    (net (code "232") (name "TEC_SWEN_2") (class "Default")
      (node (ref "R33") (pin "1") (pinfunction "1_1") (pintype "passive"))
    )
    (net (code "233") (name "TEC_SWEN_3") (class "Default")
      (node (ref "R64") (pin "2") (pinfunction "2_2") (pintype "passive"))
    )
    (net (code "234") (name "TEC_SWEN_4") (class "Default")
      (node (ref "R66") (pin "2") (pinfunction "2_2") (pintype "passive"))
    )
    (net (code "235") (name "TEC_nCS_1") (class "Default")
      (node (ref "R95") (pin "2") (pinfunction "2_2") (pintype "passive"))
    )
    (net (code "236") (name "TEC_nCS_2") (class "Default")
      (node (ref "R98") (pin "2") (pinfunction "2_2") (pintype "passive"))
    )
    (net (code "237") (name "TEC_nCS_3") (class "Default")
      (node (ref "R100") (pin "2") (pinfunction "2_2") (pintype "passive"))
    )
    (net (code "238") (name "TEC_nCS_4") (class "Default")
      (node (ref "R29") (pin "1") (pinfunction "1_1") (pintype "passive"))
    )
    (net (code "241") (name "unconnected-(J3-Pad1)") (class "Default")
      (node (ref "J3") (pin "1") (pinfunction "1_1") (pintype "passive"))
    )
    (net (code "242") (name "unconnected-(J3-Pad7)") (class "Default")
      (node (ref "J3") (pin "7") (pinfunction "7_7") (pintype "passive"))
    )
    (net (code "243") (name "unconnected-(U3-PA05-Pad73)") (class "Default")
      (node (ref "U3") (pin "73") (pinfunction "PA05_73") (pintype "bidirectional"))
    )
    (net (code "244") (name "unconnected-(U3-PA06-Pad114)") (class "Default")
      (node (ref "U3") (pin "114") (pinfunction "PA06_114") (pintype "bidirectional"))
    )
    (net (code "245") (name "unconnected-(U3-PA21-Pad32)") (class "Default")
      (node (ref "U3") (pin "32") (pinfunction "PA21_32") (pintype "bidirectional"))
    )
  )
)
